# ECU_Sheet.net
KiCad netlist of a schematic drawn in Altium Designer
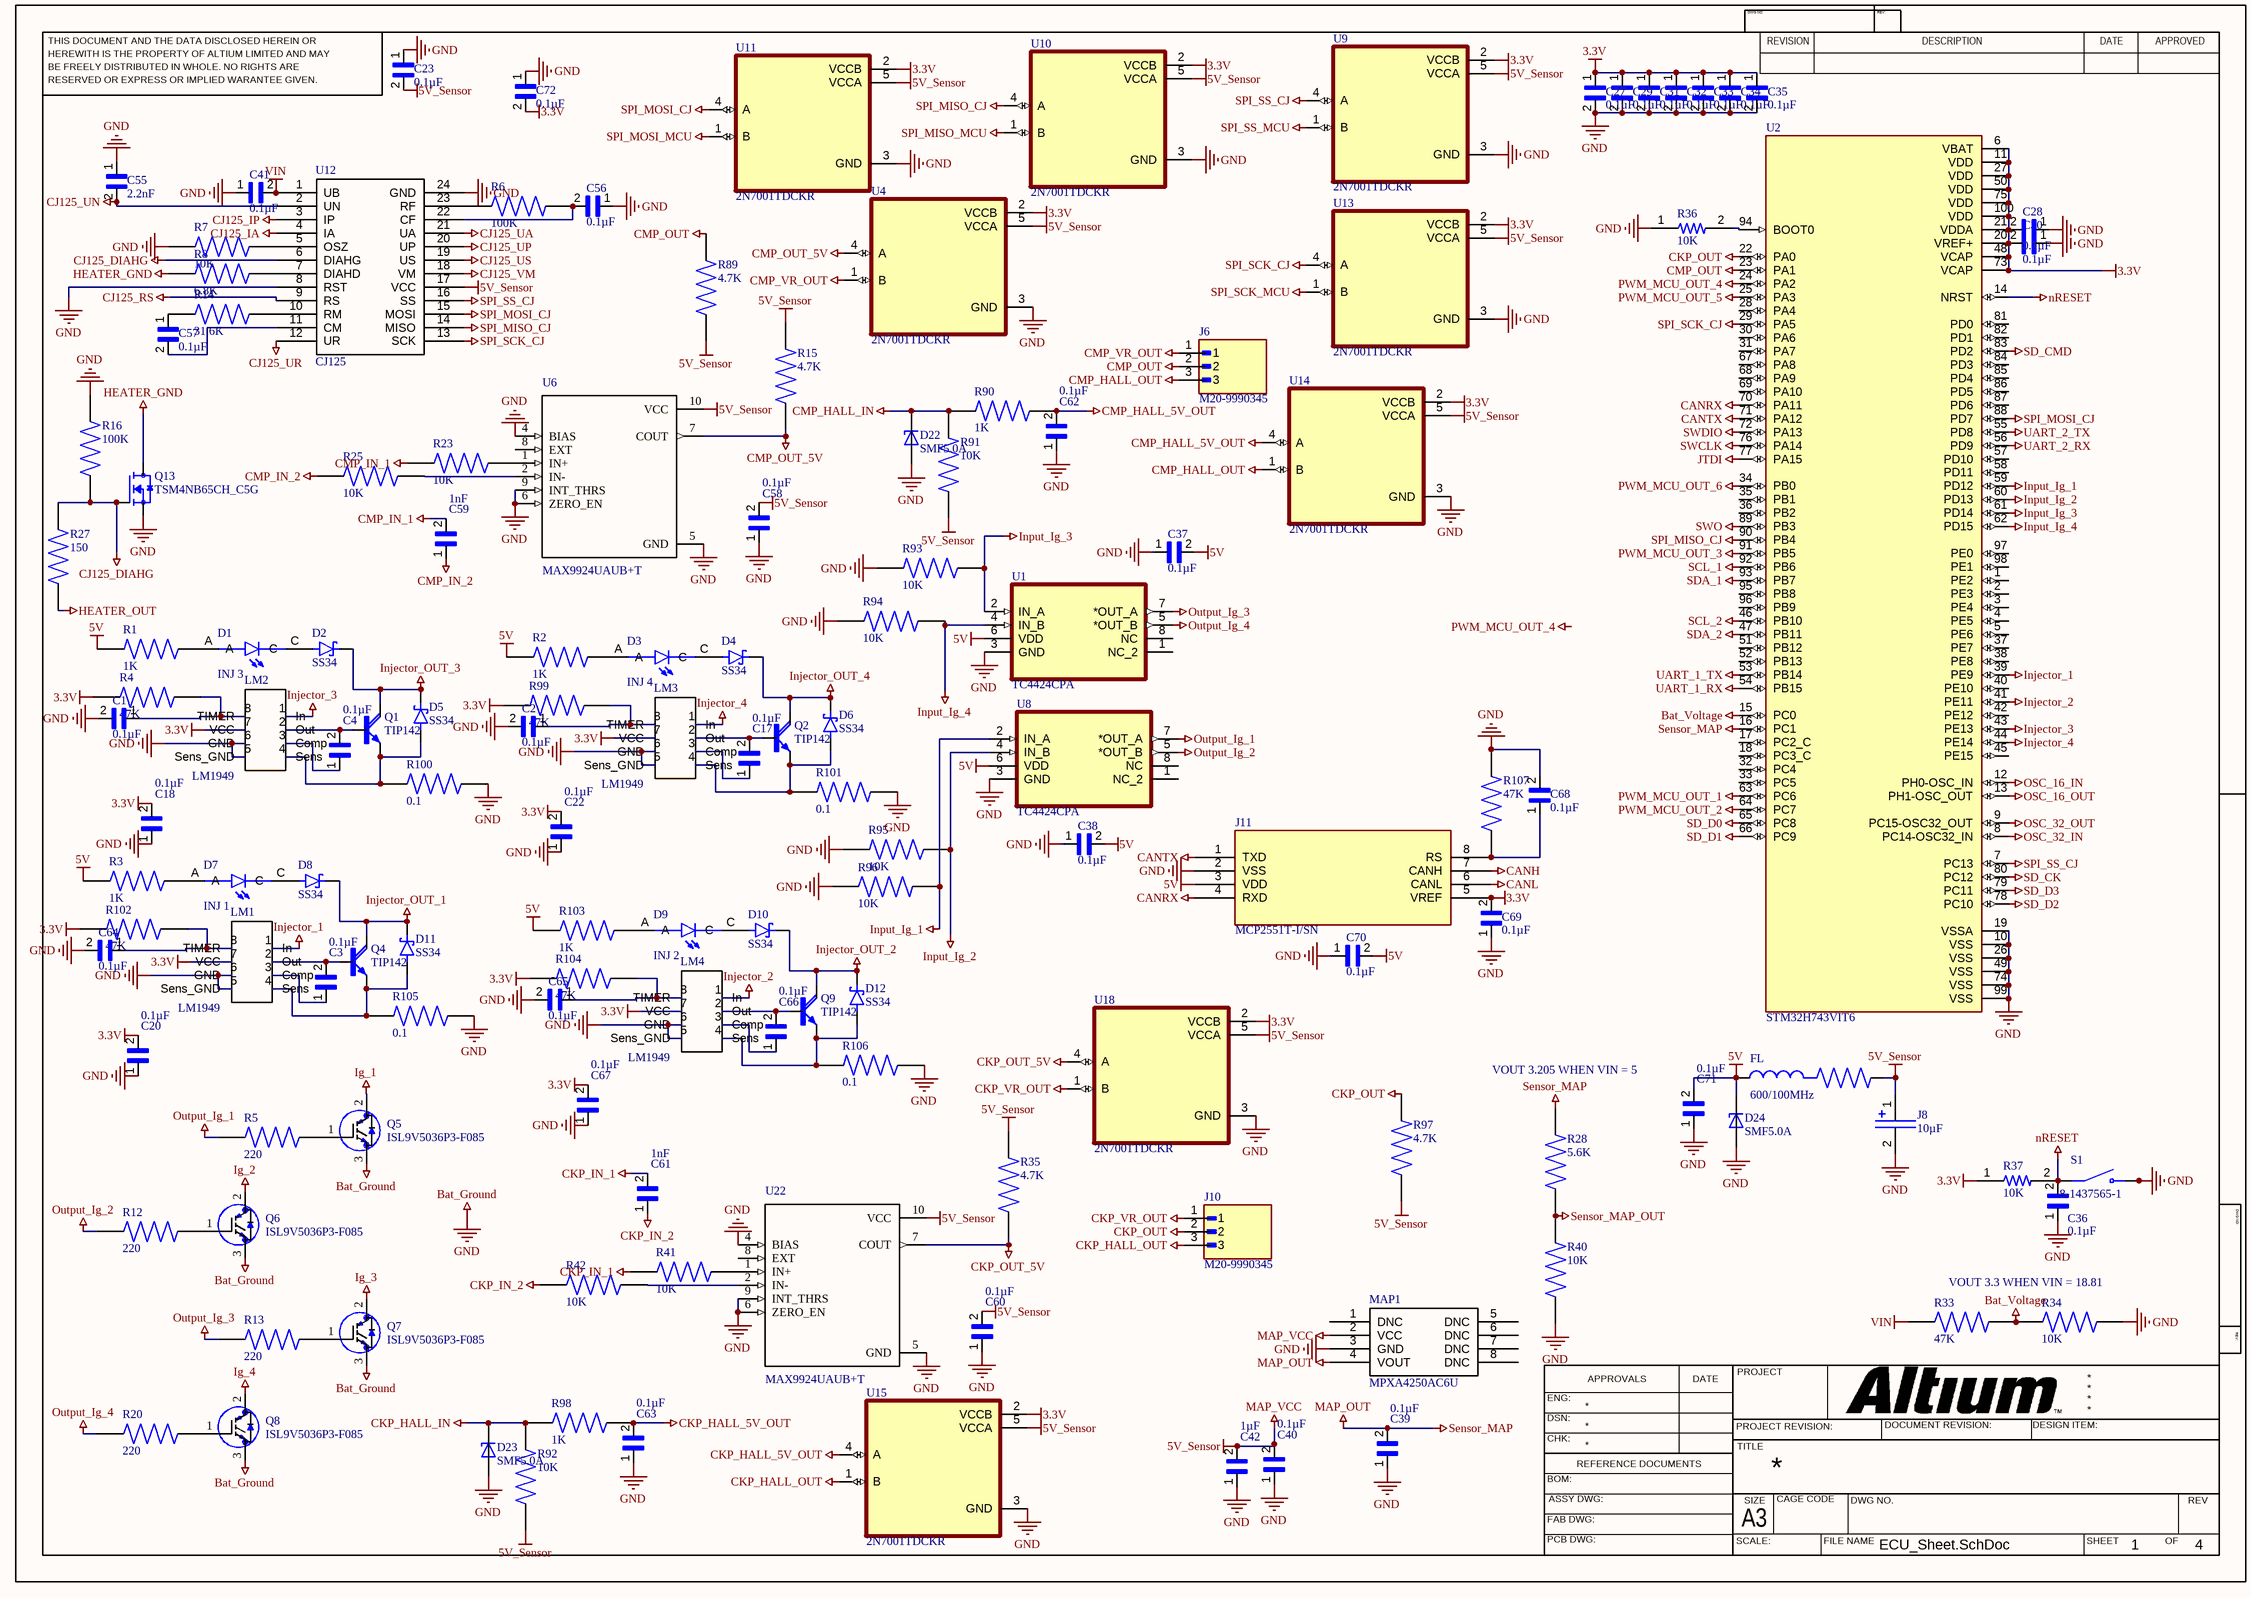
[diagram p0: ECU_Sheet.SchDoc]

(export (version "E")
  (design (tool "Eeschema 10.0.6"))
  (components
    (comp (ref "C1")
      (value "0.1µF")
      (footprint "CAPC1608X90N")
      (description "Multilayer Ceramic Capacitors MLCC - SMD/SMT")
      (fields (field (name "MP") "06035C104MAZ2A"))
      (libsource (lib "") (part "06035C104MAZ2A_1"))
    )
    (comp (ref "C2")
      (value "0.1µF")
      (footprint "CAPC1608X90N")
      (description "Multilayer Ceramic Capacitors MLCC - SMD/SMT")
      (fields (field (name "MP") "06035C104MAZ2A"))
      (libsource (lib "") (part "06035C104MAZ2A_1"))
    )
    (comp (ref "C3")
      (value "0.1µF")
      (footprint "CAPC1608X90N")
      (description "Multilayer Ceramic Capacitors MLCC - SMD/SMT")
      (fields (field (name "MP") "06035C104MAZ2A"))
      (libsource (lib "06035C104MAZ2A") (part "06035C104MAZ2A"))
    )
    (comp (ref "C4")
      (value "0.1µF")
      (footprint "CAPC1608X90N")
      (description "Multilayer Ceramic Capacitors MLCC - SMD/SMT")
      (fields (field (name "MP") "06035C104MAZ2A"))
      (libsource (lib "06035C104MAZ2A") (part "06035C104MAZ2A"))
    )
    (comp (ref "C17")
      (value "0.1µF")
      (footprint "CAPC1608X90N")
      (description "Multilayer Ceramic Capacitors MLCC - SMD/SMT")
      (fields (field (name "MP") "06035C104MAZ2A"))
      (libsource (lib "06035C104MAZ2A") (part "06035C104MAZ2A"))
    )
    (comp (ref "C18")
      (value "0.1µF")
      (footprint "CAPC1608X90N")
      (description "Multilayer Ceramic Capacitors MLCC - SMD/SMT")
      (fields (field (name "MP") "06035C104MAZ2A"))
      (libsource (lib "06035C104MAZ2A") (part "06035C104MAZ2A"))
    )
    (comp (ref "C20")
      (value "0.1µF")
      (footprint "CAPC1608X90N")
      (description "Multilayer Ceramic Capacitors MLCC - SMD/SMT")
      (fields (field (name "MP") "06035C104MAZ2A"))
      (libsource (lib "06035C104MAZ2A") (part "06035C104MAZ2A"))
    )
    (comp (ref "C22")
      (value "0.1µF")
      (footprint "CAPC1608X90N")
      (description "Multilayer Ceramic Capacitors MLCC - SMD/SMT")
      (fields (field (name "MP") "06035C104MAZ2A"))
      (libsource (lib "06035C104MAZ2A") (part "06035C104MAZ2A"))
    )
    (comp (ref "C23")
      (value "0.1µF")
      (footprint "CAPC1608X90N")
      (description "Multilayer Ceramic Capacitors MLCC - SMD/SMT")
      (fields (field (name "MP") "06035C104MAZ2A"))
      (libsource (lib "") (part "06035C104MAZ2A_2"))
    )
    (comp (ref "C27")
      (value "0.1µF")
      (footprint "CAPC1608X90N")
      (description "Multilayer Ceramic Capacitors MLCC - SMD/SMT")
      (fields (field (name "MP") "06035C104MAZ2A"))
      (libsource (lib "") (part "06035C104MAZ2A_2"))
    )
    (comp (ref "C28")
      (value "0.1µF")
      (footprint "CAPC1608X90N")
      (description "Multilayer Ceramic Capacitors MLCC - SMD/SMT")
      (fields (field (name "MP") "06035C104MAZ2A"))
      (libsource (lib "") (part "06035C104MAZ2A_1"))
    )
    (comp (ref "C29")
      (value "0.1µF")
      (footprint "CAPC1608X90N")
      (description "Multilayer Ceramic Capacitors MLCC - SMD/SMT")
      (fields (field (name "MP") "06035C104MAZ2A"))
      (libsource (lib "") (part "06035C104MAZ2A_2"))
    )
    (comp (ref "C30")
      (value "0.1µF")
      (footprint "CAPC1608X90N")
      (description "Multilayer Ceramic Capacitors MLCC - SMD/SMT")
      (fields (field (name "MP") "06035C104MAZ2A"))
      (libsource (lib "") (part "06035C104MAZ2A_1"))
    )
    (comp (ref "C31")
      (value "0.1µF")
      (footprint "CAPC1608X90N")
      (description "Multilayer Ceramic Capacitors MLCC - SMD/SMT")
      (fields (field (name "MP") "06035C104MAZ2A"))
      (libsource (lib "") (part "06035C104MAZ2A_2"))
    )
    (comp (ref "C32")
      (value "0.1µF")
      (footprint "CAPC1608X90N")
      (description "Multilayer Ceramic Capacitors MLCC - SMD/SMT")
      (fields (field (name "MP") "06035C104MAZ2A"))
      (libsource (lib "") (part "06035C104MAZ2A_2"))
    )
    (comp (ref "C33")
      (value "0.1µF")
      (footprint "CAPC1608X90N")
      (description "Multilayer Ceramic Capacitors MLCC - SMD/SMT")
      (fields (field (name "MP") "06035C104MAZ2A"))
      (libsource (lib "") (part "06035C104MAZ2A_2"))
    )
    (comp (ref "C34")
      (value "0.1µF")
      (footprint "CAPC1608X90N")
      (description "Multilayer Ceramic Capacitors MLCC - SMD/SMT")
      (fields (field (name "MP") "06035C104MAZ2A"))
      (libsource (lib "") (part "06035C104MAZ2A_2"))
    )
    (comp (ref "C35")
      (value "0.1µF")
      (footprint "CAPC1608X90N")
      (description "Multilayer Ceramic Capacitors MLCC - SMD/SMT")
      (fields (field (name "MP") "06035C104MAZ2A"))
      (libsource (lib "") (part "06035C104MAZ2A_2"))
    )
    (comp (ref "C36")
      (value "0.1µF")
      (footprint "CAPC1608X90N")
      (description "Multilayer Ceramic Capacitors MLCC - SMD/SMT")
      (fields (field (name "MP") "06035C104MAZ2A"))
      (libsource (lib "06035C104MAZ2A") (part "06035C104MAZ2A"))
    )
    (comp (ref "C37")
      (value "0.1µF")
      (footprint "CAPC1608X90N")
      (description "Multilayer Ceramic Capacitors MLCC - SMD/SMT")
      (fields (field (name "MP") "06035C104MAZ2A"))
      (libsource (lib "") (part "06035C104MAZ2A_3"))
    )
    (comp (ref "C38")
      (value "0.1µF")
      (footprint "CAPC1608X90N")
      (description "Multilayer Ceramic Capacitors MLCC - SMD/SMT")
      (fields (field (name "MP") "06035C104MAZ2A"))
      (libsource (lib "") (part "06035C104MAZ2A_3"))
    )
    (comp (ref "C39")
      (value "0.1µF")
      (footprint "CAPC1608X90N")
      (description "Multilayer Ceramic Capacitors MLCC - SMD/SMT")
      (fields (field (name "MP") "06035C104MAZ2A"))
      (libsource (lib "06035C104MAZ2A") (part "06035C104MAZ2A"))
    )
    (comp (ref "C40")
      (value "0.1µF")
      (footprint "CAPC1608X90N")
      (description "Multilayer Ceramic Capacitors MLCC - SMD/SMT")
      (fields (field (name "MP") "06035C104MAZ2A"))
      (libsource (lib "06035C104MAZ2A") (part "06035C104MAZ2A"))
    )
    (comp (ref "C41")
      (value "0.1µF")
      (footprint "CAPC1608X90N")
      (description "Multilayer Ceramic Capacitors MLCC - SMD/SMT")
      (fields (field (name "MP") "06035C104MAZ2A"))
      (libsource (lib "") (part "06035C104MAZ2A_3"))
    )
    (comp (ref "C42")
      (value "1µF")
      (footprint "CAPC1608X90N")
      (description "Multilayer Ceramic Capacitors MLCC - SMD/SMT")
      (fields (field (name "MP") "06035C104MAZ2A"))
      (libsource (lib "06035C104MAZ2A") (part "06035C104MAZ2A"))
    )
    (comp (ref "C55")
      (value "2.2nF")
      (footprint "CAPC1608X90N")
      (description "Multilayer Ceramic Capacitors MLCC - SMD/SMT")
      (fields (field (name "MP") "06035C104MAZ2A"))
      (libsource (lib "") (part "06035C104MAZ2A_2"))
    )
    (comp (ref "C56")
      (value "0.1µF")
      (footprint "CAPC1608X90N")
      (description "Multilayer Ceramic Capacitors MLCC - SMD/SMT")
      (fields (field (name "MP") "06035C104MAZ2A"))
      (libsource (lib "") (part "06035C104MAZ2A_1"))
    )
    (comp (ref "C57")
      (value "0.1µF")
      (footprint "CAPC1608X90N")
      (description "Multilayer Ceramic Capacitors MLCC - SMD/SMT")
      (fields (field (name "MP") "06035C104MAZ2A"))
      (libsource (lib "") (part "06035C104MAZ2A_2"))
    )
    (comp (ref "C58")
      (value "0.1µF")
      (footprint "CAPC1608X90N")
      (description "Multilayer Ceramic Capacitors MLCC - SMD/SMT")
      (fields (field (name "MP") "06035C104MAZ2A"))
      (libsource (lib "06035C104MAZ2A") (part "06035C104MAZ2A"))
    )
    (comp (ref "C59")
      (value "1nF")
      (footprint "CAPC1608X90N")
      (description "Multilayer Ceramic Capacitors MLCC - SMD/SMT")
      (fields (field (name "MP") "06035C104MAZ2A"))
      (libsource (lib "06035C104MAZ2A") (part "06035C104MAZ2A"))
    )
    (comp (ref "C60")
      (value "0.1µF")
      (footprint "CAPC1608X90N")
      (description "Multilayer Ceramic Capacitors MLCC - SMD/SMT")
      (fields (field (name "MP") "06035C104MAZ2A"))
      (libsource (lib "06035C104MAZ2A") (part "06035C104MAZ2A"))
    )
    (comp (ref "C61")
      (value "1nF")
      (footprint "CAPC1608X90N")
      (description "Multilayer Ceramic Capacitors MLCC - SMD/SMT")
      (fields (field (name "MP") "06035C104MAZ2A"))
      (libsource (lib "06035C104MAZ2A") (part "06035C104MAZ2A"))
    )
    (comp (ref "C62")
      (value "0.1µF")
      (footprint "CAPC1608X90N")
      (description "Multilayer Ceramic Capacitors MLCC - SMD/SMT")
      (fields (field (name "MP") "06035C104MAZ2A"))
      (libsource (lib "06035C104MAZ2A") (part "06035C104MAZ2A"))
    )
    (comp (ref "C63")
      (value "0.1µF")
      (footprint "CAPC1608X90N")
      (description "Multilayer Ceramic Capacitors MLCC - SMD/SMT")
      (fields (field (name "MP") "06035C104MAZ2A"))
      (libsource (lib "06035C104MAZ2A") (part "06035C104MAZ2A"))
    )
    (comp (ref "C64")
      (value "0.1µF")
      (footprint "CAPC1608X90N")
      (description "Multilayer Ceramic Capacitors MLCC - SMD/SMT")
      (fields (field (name "MP") "06035C104MAZ2A"))
      (libsource (lib "") (part "06035C104MAZ2A_1"))
    )
    (comp (ref "C65")
      (value "0.1µF")
      (footprint "CAPC1608X90N")
      (description "Multilayer Ceramic Capacitors MLCC - SMD/SMT")
      (fields (field (name "MP") "06035C104MAZ2A"))
      (libsource (lib "") (part "06035C104MAZ2A_1"))
    )
    (comp (ref "C66")
      (value "0.1µF")
      (footprint "CAPC1608X90N")
      (description "Multilayer Ceramic Capacitors MLCC - SMD/SMT")
      (fields (field (name "MP") "06035C104MAZ2A"))
      (libsource (lib "06035C104MAZ2A") (part "06035C104MAZ2A"))
    )
    (comp (ref "C67")
      (value "0.1µF")
      (footprint "CAPC1608X90N")
      (description "Multilayer Ceramic Capacitors MLCC - SMD/SMT")
      (fields (field (name "MP") "06035C104MAZ2A"))
      (libsource (lib "06035C104MAZ2A") (part "06035C104MAZ2A"))
    )
    (comp (ref "C68")
      (value "0.1µF")
      (footprint "CAPC1608X90N")
      (description "Multilayer Ceramic Capacitors MLCC - SMD/SMT")
      (fields (field (name "MP") "06035C104MAZ2A"))
      (libsource (lib "06035C104MAZ2A") (part "06035C104MAZ2A"))
    )
    (comp (ref "C69")
      (value "0.1µF")
      (footprint "CAPC1608X90N")
      (description "Multilayer Ceramic Capacitors MLCC - SMD/SMT")
      (fields (field (name "MP") "06035C104MAZ2A"))
      (libsource (lib "06035C104MAZ2A") (part "06035C104MAZ2A"))
    )
    (comp (ref "C70")
      (value "0.1µF")
      (footprint "CAPC1608X90N")
      (description "Multilayer Ceramic Capacitors MLCC - SMD/SMT")
      (fields (field (name "MP") "06035C104MAZ2A"))
      (libsource (lib "") (part "06035C104MAZ2A_3"))
    )
    (comp (ref "C71")
      (value "0.1µF")
      (footprint "CAPC1608X90N")
      (description "Multilayer Ceramic Capacitors MLCC - SMD/SMT")
      (fields (field (name "MP") "06035C104MAZ2A"))
      (libsource (lib "06035C104MAZ2A") (part "06035C104MAZ2A"))
    )
    (comp (ref "C72")
      (value "0.1µF")
      (footprint "CAPC1608X90N")
      (description "Multilayer Ceramic Capacitors MLCC - SMD/SMT")
      (fields (field (name "MP") "06035C104MAZ2A"))
      (libsource (lib "") (part "06035C104MAZ2A_2"))
    )
    (comp (ref "D1")
      (value "INJ 3")
      (footprint "LEDC2012X70N")
      (description "LED Uni-Color Green 4-Pin Chip 0805 T/R")
      (fields (field (name "MP") "597-3305-607F"))
      (libsource (lib "597-3305-607F") (part "597-3305-607F"))
    )
    (comp (ref "D2")
      (value "SS34")
      (footprint "DIO_SS34")
      (description "3A, 40V, Schottky Rectifier")
      (fields (field (name "MF") "Taiwan Semiconductor"))
      (libsource (lib "SS34") (part "SS34"))
    )
    (comp (ref "D3")
      (value "INJ 4")
      (footprint "LEDC2012X70N")
      (description "LED Uni-Color Green 4-Pin Chip 0805 T/R")
      (fields (field (name "MP") "597-3305-607F"))
      (libsource (lib "597-3305-607F") (part "597-3305-607F"))
    )
    (comp (ref "D4")
      (value "SS34")
      (footprint "DIO_SS34")
      (description "3A, 40V, Schottky Rectifier")
      (fields (field (name "MF") "Taiwan Semiconductor"))
      (libsource (lib "SS34") (part "SS34"))
    )
    (comp (ref "D5")
      (value "SS34")
      (footprint "DIO_SS34")
      (description "3A, 40V, Schottky Rectifier")
      (fields (field (name "MF") "Taiwan Semiconductor"))
      (libsource (lib "SS34") (part "SS34"))
    )
    (comp (ref "D6")
      (value "SS34")
      (footprint "DIO_SS34")
      (description "3A, 40V, Schottky Rectifier")
      (fields (field (name "MF") "Taiwan Semiconductor"))
      (libsource (lib "SS34") (part "SS34"))
    )
    (comp (ref "D7")
      (value "INJ 1")
      (footprint "LEDC2012X70N")
      (description "LED Uni-Color Green 4-Pin Chip 0805 T/R")
      (fields (field (name "MP") "597-3305-607F"))
      (libsource (lib "597-3305-607F") (part "597-3305-607F"))
    )
    (comp (ref "D8")
      (value "SS34")
      (footprint "DIO_SS34")
      (description "3A, 40V, Schottky Rectifier")
      (fields (field (name "MF") "Taiwan Semiconductor"))
      (libsource (lib "SS34") (part "SS34"))
    )
    (comp (ref "D9")
      (value "INJ 2")
      (footprint "LEDC2012X70N")
      (description "LED Uni-Color Green 4-Pin Chip 0805 T/R")
      (fields (field (name "MP") "597-3305-607F"))
      (libsource (lib "597-3305-607F") (part "597-3305-607F"))
    )
    (comp (ref "D10")
      (value "SS34")
      (footprint "DIO_SS34")
      (description "3A, 40V, Schottky Rectifier")
      (fields (field (name "MF") "Taiwan Semiconductor"))
      (libsource (lib "SS34") (part "SS34"))
    )
    (comp (ref "D11")
      (value "SS34")
      (footprint "DIO_SS34")
      (description "3A, 40V, Schottky Rectifier")
      (fields (field (name "MF") "Taiwan Semiconductor"))
      (libsource (lib "SS34") (part "SS34"))
    )
    (comp (ref "D12")
      (value "SS34")
      (footprint "DIO_SS34")
      (description "3A, 40V, Schottky Rectifier")
      (fields (field (name "MF") "Taiwan Semiconductor"))
      (libsource (lib "SS34") (part "SS34"))
    )
    (comp (ref "D22")
      (value "SMF5.0A")
      (footprint "SODFL3718X102N")
      (description "200W, 6.7V, 5%, Unidirectional, TVS")
      (fields (field (name "MF") "Taiwan Semiconductor"))
      (libsource (lib "SMF5.0A") (part "SMF5.0A"))
    )
    (comp (ref "D23")
      (value "SMF5.0A")
      (footprint "SODFL3718X102N")
      (description "200W, 6.7V, 5%, Unidirectional, TVS")
      (fields (field (name "MF") "Taiwan Semiconductor"))
      (libsource (lib "SMF5.0A") (part "SMF5.0A"))
    )
    (comp (ref "D24")
      (value "SMF5.0A")
      (footprint "SODFL3718X102N")
      (description "200W, 6.7V, 5%, Unidirectional, TVS")
      (fields (field (name "MF") "Taiwan Semiconductor"))
      (libsource (lib "SMF5.0A") (part "SMF5.0A"))
    )
    (comp (ref "FL")
      (value "600/100MHz")
      (footprint "BEADC1608X95N")
      (description "600 Ohms @ 100MHz 1 Ferrite Bead 0603 _1608 Metric_ 700mA")
      (fields (field (name "MF") "Murata") (field (name "MP") "BLM18DN601SZ1D"))
      (libsource (lib "BLM18DN601SZ1D") (part "BLM18DN601SZ1D"))
    )
    (comp (ref "J6")
      (value "M20-9990345")
      (footprint "HARWIN_M20-9990345")
      (fields (field (name "MF") "Harwin"))
      (libsource (lib "M20-9990345") (part "M20-9990345"))
    )
    (comp (ref "J8")
      (value "10µF")
      (footprint "T491A106K010AT")
      (fields (field (name "MF") "KEMET") (field (name "MP") "T491A106K010AT"))
      (libsource (lib "T491A106K010AT") (part "T491A106K010AT"))
    )
    (comp (ref "J10")
      (value "M20-9990345")
      (footprint "HARWIN_M20-9990345")
      (fields (field (name "MF") "Harwin"))
      (libsource (lib "M20-9990345") (part "M20-9990345"))
    )
    (comp (ref "J11")
      (value "MCP2551T-I/SN")
      (footprint "SOIC8-N_MC")
      (fields (field (name "MF") "Microchip"))
      (libsource (lib "MCP2551T-I_SN") (part "MCP2551T-I/SN"))
    )
    (comp (ref "LM1")
      (value "LM1949")
      (footprint "DIP794W45P254L959H508Q8")
      (libsource (lib "LM1949") (part "Component_1"))
    )
    (comp (ref "LM2")
      (value "LM1949")
      (footprint "DIP794W45P254L959H508Q8")
      (libsource (lib "LM1949") (part "Component_1"))
    )
    (comp (ref "LM3")
      (value "LM1949")
      (footprint "DIP794W45P254L959H508Q8")
      (libsource (lib "LM1949") (part "Component_1"))
    )
    (comp (ref "LM4")
      (value "LM1949")
      (footprint "DIP794W45P254L959H508Q8")
      (libsource (lib "LM1949") (part "Component_1"))
    )
    (comp (ref "MAP1")
      (value "MPXA4250AC6U")
      (footprint "SOIC127P1041X990-8N:SOIC127P1041X990-8N")
      (libsource (lib "MPXA4250A") (part "MPXA4250AC6U"))
    )
    (comp (ref "Q1")
      (value "TIP142")
      (footprint "SOT93")
      (description "Bipolar (BJT) Transistor NPN - Darlington 100 V 10 A - 125 W Through Hole TO-247-3")
      (fields (field (name "MF") "ON Semiconductor"))
      (libsource (lib "TIP142") (part "TIP142"))
    )
    (comp (ref "Q2")
      (value "TIP142")
      (footprint "SOT93")
      (description "Bipolar (BJT) Transistor NPN - Darlington 100 V 10 A - 125 W Through Hole TO-247-3")
      (fields (field (name "MF") "ON Semiconductor"))
      (libsource (lib "TIP142") (part "TIP142"))
    )
    (comp (ref "Q4")
      (value "TIP142")
      (footprint "SOT93")
      (description "Bipolar (BJT) Transistor NPN - Darlington 100 V 10 A - 125 W Through Hole TO-247-3")
      (fields (field (name "MF") "ON Semiconductor"))
      (libsource (lib "TIP142") (part "TIP142"))
    )
    (comp (ref "Q5")
      (value "ISL9V5036P3-F085")
      (footprint "*TO254P470X1016X2019-3P")
      (libsource (lib "ISL9V5036P3-F085") (part "ISL9V5036P3-F085"))
    )
    (comp (ref "Q6")
      (value "ISL9V5036P3-F085")
      (footprint "*TO254P470X1016X2019-3P")
      (libsource (lib "ISL9V5036P3-F085") (part "ISL9V5036P3-F085"))
    )
    (comp (ref "Q7")
      (value "ISL9V5036P3-F085")
      (footprint "*TO254P470X1016X2019-3P")
      (libsource (lib "ISL9V5036P3-F085") (part "ISL9V5036P3-F085"))
    )
    (comp (ref "Q8")
      (value "ISL9V5036P3-F085")
      (footprint "*TO254P470X1016X2019-3P")
      (libsource (lib "ISL9V5036P3-F085") (part "ISL9V5036P3-F085"))
    )
    (comp (ref "Q9")
      (value "TIP142")
      (footprint "SOT93")
      (description "Bipolar (BJT) Transistor NPN - Darlington 100 V 10 A - 125 W Through Hole TO-247-3")
      (fields (field (name "MF") "ON Semiconductor"))
      (libsource (lib "TIP142") (part "TIP142"))
    )
    (comp (ref "Q13")
      (value "TSM4NB65CH_C5G")
      (footprint "TO228P680X240X837-3")
      (description "650V, 4A, Single N-Channel Power MOSFET")
      (fields (field (name "MF") "Taiwan Semiconductor") (field (name "MP") "TSM4NB65CH C5G"))
      (libsource (lib "TSM4NB65CH_C5G") (part "TSM4NB65CH_C5G"))
    )
    (comp (ref "R1")
      (value "1K")
      (footprint "RESC3116X65N")
      (fields (field (name "MF") "Yageo Corporation") (field (name "MP") "RC1206JR071KL"))
      (libsource (lib "RC1206JR-071KL") (part "RC1206JR-071KL"))
    )
    (comp (ref "R2")
      (value "1K")
      (footprint "RESC3116X65N")
      (fields (field (name "MF") "Yageo Corporation") (field (name "MP") "RC1206JR071KL"))
      (libsource (lib "RC1206JR-071KL") (part "RC1206JR-071KL"))
    )
    (comp (ref "R3")
      (value "1K")
      (footprint "RESC3116X65N")
      (fields (field (name "MF") "Yageo Corporation") (field (name "MP") "RC1206JR071KL"))
      (libsource (lib "RC1206JR-071KL") (part "RC1206JR-071KL"))
    )
    (comp (ref "R4")
      (value "47K")
      (footprint "RESC3116X65N")
      (fields (field (name "MP") "AA1206JR-07470RL"))
      (libsource (lib "AA1206JR-07470RL") (part "AA1206JR-07470RL"))
    )
    (comp (ref "R5")
      (value "220")
      (footprint "RES_ERJP08J221V")
      (fields (field (name "MP") "ERJP08J221V"))
      (libsource (lib "ERJP08J221V") (part "ERJP08J221V"))
    )
    (comp (ref "R6")
      (value "100K")
      (footprint "RESC3116X65N")
      (fields (field (name "MP") "AA1206JR-07470RL"))
      (libsource (lib "AA1206JR-07470RL") (part "AA1206JR-07470RL"))
    )
    (comp (ref "R7")
      (value "10K")
      (footprint "RESC3116X65N")
      (fields (field (name "MP") "AA1206JR-07470RL"))
      (libsource (lib "AA1206JR-07470RL") (part "AA1206JR-07470RL"))
    )
    (comp (ref "R8")
      (value "6.8K")
      (footprint "RESC3116X65N")
      (fields (field (name "MP") "AA1206JR-07470RL"))
      (libsource (lib "AA1206JR-07470RL") (part "AA1206JR-07470RL"))
    )
    (comp (ref "R12")
      (value "220")
      (footprint "RES_ERJP08J221V")
      (fields (field (name "MP") "ERJP08J221V"))
      (libsource (lib "ERJP08J221V") (part "ERJP08J221V"))
    )
    (comp (ref "R13")
      (value "220")
      (footprint "RES_ERJP08J221V")
      (fields (field (name "MP") "ERJP08J221V"))
      (libsource (lib "ERJP08J221V") (part "ERJP08J221V"))
    )
    (comp (ref "R14")
      (value "31.6K")
      (footprint "RESC3116X65N")
      (fields (field (name "MP") "AA1206JR-07470RL"))
      (libsource (lib "AA1206JR-07470RL") (part "AA1206JR-07470RL"))
    )
    (comp (ref "R15")
      (value "4.7K")
      (footprint "RESC3116X65N")
      (fields (field (name "MP") "AA1206JR-07470RL"))
      (libsource (lib "AA1206JR-07470RL") (part "AA1206JR-07470RL"))
    )
    (comp (ref "R16")
      (value "100K")
      (footprint "RESC3116X65N")
      (fields (field (name "MP") "AA1206JR-07470RL"))
      (libsource (lib "AA1206JR-07470RL") (part "AA1206JR-07470RL"))
    )
    (comp (ref "R20")
      (value "220")
      (footprint "RES_ERJP08J221V")
      (fields (field (name "MP") "ERJP08J221V"))
      (libsource (lib "ERJP08J221V") (part "ERJP08J221V"))
    )
    (comp (ref "R23")
      (value "10K")
      (footprint "RESC3116X65N")
      (fields (field (name "MP") "AA1206JR-07470RL"))
      (libsource (lib "AA1206JR-07470RL") (part "AA1206JR-07470RL"))
    )
    (comp (ref "R25")
      (value "10K")
      (footprint "RESC3116X65N")
      (fields (field (name "MP") "AA1206JR-07470RL"))
      (libsource (lib "AA1206JR-07470RL") (part "AA1206JR-07470RL"))
    )
    (comp (ref "R27")
      (value "150")
      (footprint "RESC3116X65N")
      (fields (field (name "MP") "AA1206JR-07470RL"))
      (libsource (lib "AA1206JR-07470RL") (part "AA1206JR-07470RL"))
    )
    (comp (ref "R28")
      (value "5.6K")
      (footprint "RESC3116X65N")
      (fields (field (name "MP") "AA1206JR-07470RL"))
      (libsource (lib "AA1206JR-07470RL") (part "AA1206JR-07470RL"))
    )
    (comp (ref "R33")
      (value "47K")
      (footprint "RESC3116X65N")
      (fields (field (name "MP") "AA1206JR-07470RL"))
      (libsource (lib "AA1206JR-07470RL") (part "AA1206JR-07470RL"))
    )
    (comp (ref "R34")
      (value "10K")
      (footprint "RESC3116X65N")
      (fields (field (name "MP") "AA1206JR-07470RL"))
      (libsource (lib "AA1206JR-07470RL") (part "AA1206JR-07470RL"))
    )
    (comp (ref "R35")
      (value "4.7K")
      (footprint "RESC3116X65N")
      (fields (field (name "MP") "AA1206JR-07470RL"))
      (libsource (lib "AA1206JR-07470RL") (part "AA1206JR-07470RL"))
    )
    (comp (ref "R36")
      (value "10K")
      (footprint "RESC1608X50N")
      (description "Thin Film Resistors - SMD 10K OHM .1% 25PPM")
      (fields (field (name "MP") "RP73PF1J10KBTDF") (field (name "TOLERANCE") ".1%"))
      (libsource (lib "RP73PF1J10KBTDF") (part "RP73PF1J10KBTDF"))
    )
    (comp (ref "R37")
      (value "10K")
      (footprint "RESC1608X50N")
      (description "Thin Film Resistors - SMD 10K OHM .1% 25PPM")
      (fields (field (name "MP") "RP73PF1J10KBTDF") (field (name "TOLERANCE") ".1%"))
      (libsource (lib "RP73PF1J10KBTDF") (part "RP73PF1J10KBTDF"))
    )
    (comp (ref "R40")
      (value "10K")
      (footprint "RESC3116X65N")
      (fields (field (name "MP") "AA1206JR-07470RL"))
      (libsource (lib "AA1206JR-07470RL") (part "AA1206JR-07470RL"))
    )
    (comp (ref "R41")
      (value "10K")
      (footprint "RESC3116X65N")
      (fields (field (name "MP") "AA1206JR-07470RL"))
      (libsource (lib "AA1206JR-07470RL") (part "AA1206JR-07470RL"))
    )
    (comp (ref "R42")
      (value "10K")
      (footprint "RESC3116X65N")
      (fields (field (name "MP") "AA1206JR-07470RL"))
      (libsource (lib "AA1206JR-07470RL") (part "AA1206JR-07470RL"))
    )
    (comp (ref "R89")
      (value "4.7K")
      (footprint "RESC3116X65N")
      (fields (field (name "MP") "AA1206JR-07470RL"))
      (libsource (lib "AA1206JR-07470RL") (part "AA1206JR-07470RL"))
    )
    (comp (ref "R90")
      (value "1K")
      (footprint "RESC3116X65N")
      (fields (field (name "MP") "AA1206JR-07470RL"))
      (libsource (lib "AA1206JR-07470RL") (part "AA1206JR-07470RL"))
    )
    (comp (ref "R91")
      (value "10K")
      (footprint "RESC3116X65N")
      (fields (field (name "MP") "AA1206JR-07470RL"))
      (libsource (lib "AA1206JR-07470RL") (part "AA1206JR-07470RL"))
    )
    (comp (ref "R92")
      (value "10K")
      (footprint "RESC3116X65N")
      (fields (field (name "MP") "AA1206JR-07470RL"))
      (libsource (lib "AA1206JR-07470RL") (part "AA1206JR-07470RL"))
    )
    (comp (ref "R93")
      (value "10K")
      (footprint "RESC3116X65N")
      (fields (field (name "MP") "AA1206JR-07470RL"))
      (libsource (lib "AA1206JR-07470RL") (part "AA1206JR-07470RL"))
    )
    (comp (ref "R94")
      (value "10K")
      (footprint "RESC3116X65N")
      (fields (field (name "MP") "AA1206JR-07470RL"))
      (libsource (lib "AA1206JR-07470RL") (part "AA1206JR-07470RL"))
    )
    (comp (ref "R95")
      (value "10K")
      (footprint "RESC3116X65N")
      (fields (field (name "MP") "AA1206JR-07470RL"))
      (libsource (lib "AA1206JR-07470RL") (part "AA1206JR-07470RL"))
    )
    (comp (ref "R96")
      (value "10K")
      (footprint "RESC3116X65N")
      (fields (field (name "MP") "AA1206JR-07470RL"))
      (libsource (lib "AA1206JR-07470RL") (part "AA1206JR-07470RL"))
    )
    (comp (ref "R97")
      (value "4.7K")
      (footprint "RESC3116X65N")
      (fields (field (name "MP") "AA1206JR-07470RL"))
      (libsource (lib "AA1206JR-07470RL") (part "AA1206JR-07470RL"))
    )
    (comp (ref "R98")
      (value "1K")
      (footprint "RESC3116X65N")
      (fields (field (name "MP") "AA1206JR-07470RL"))
      (libsource (lib "AA1206JR-07470RL") (part "AA1206JR-07470RL"))
    )
    (comp (ref "R99")
      (value "47K")
      (footprint "RESC3116X65N")
      (fields (field (name "MP") "AA1206JR-07470RL"))
      (libsource (lib "AA1206JR-07470RL") (part "AA1206JR-07470RL"))
    )
    (comp (ref "R100")
      (value "0.1")
      (footprint "RES_ERJ6RSFR10V")
      (fields (field (name "MP") "ERJ6RSFR10V"))
      (libsource (lib "ERJ6RSFR10V") (part "ERJ6RSFR10V"))
    )
    (comp (ref "R101")
      (value "0.1")
      (footprint "RES_ERJ6RSFR10V")
      (fields (field (name "MP") "ERJ6RSFR10V"))
      (libsource (lib "ERJ6RSFR10V") (part "ERJ6RSFR10V"))
    )
    (comp (ref "R102")
      (value "47K")
      (footprint "RESC3116X65N")
      (fields (field (name "MP") "AA1206JR-07470RL"))
      (libsource (lib "AA1206JR-07470RL") (part "AA1206JR-07470RL"))
    )
    (comp (ref "R103")
      (value "1K")
      (footprint "RESC3116X65N")
      (fields (field (name "MF") "Yageo Corporation") (field (name "MP") "RC1206JR071KL"))
      (libsource (lib "RC1206JR-071KL") (part "RC1206JR-071KL"))
    )
    (comp (ref "R104")
      (value "47K")
      (footprint "RESC3116X65N")
      (fields (field (name "MP") "AA1206JR-07470RL"))
      (libsource (lib "AA1206JR-07470RL") (part "AA1206JR-07470RL"))
    )
    (comp (ref "R105")
      (value "0.1")
      (footprint "RES_ERJ6RSFR10V")
      (fields (field (name "MP") "ERJ6RSFR10V"))
      (libsource (lib "ERJ6RSFR10V") (part "ERJ6RSFR10V"))
    )
    (comp (ref "R106")
      (value "0.1")
      (footprint "RES_ERJ6RSFR10V")
      (fields (field (name "MP") "ERJ6RSFR10V"))
      (libsource (lib "ERJ6RSFR10V") (part "ERJ6RSFR10V"))
    )
    (comp (ref "R107")
      (value "47K")
      (footprint "RESC3116X65N")
      (fields (field (name "MP") "AA1206JR-07470RL"))
      (libsource (lib "AA1206JR-07470RL") (part "AA1206JR-07470RL"))
    )
    (comp (ref "S1")
      (value "8-1437565-1")
      (footprint "SW_8-1437565-1")
      (libsource (lib "8-1437565-1") (part "8-1437565-1"))
    )
    (comp (ref "U1")
      (value "TC4424CPA")
      (footprint "DIP254P762X432-8")
      (fields (field (name "MF") "Microchip"))
      (libsource (lib "TC4424CPA") (part "TC4424CPA"))
    )
    (comp (ref "U2")
      (value "STM32H743VIT6")
      (footprint "QFP50P1600X1600X160-100N")
      (fields (field (name "MF") "STMicroelectronics"))
      (libsource (lib "STM32H743VIT6") (part "STM32H743VIT6"))
    )
    (comp (ref "U4")
      (value "2N7001TDCKR")
      (footprint "SOT65P210X110-5N")
      (description "1-bit dual-supply buffered voltage signal converter")
      (fields (field (name "MF") "Texas Instruments"))
      (libsource (lib "2N7001TDCKR") (part "2N7001TDCKR"))
    )
    (comp (ref "U6")
      (value "MAX9924UAUB+T")
      (footprint "*SOP50P490X110-10N")
      (libsource (lib "MAX9924UAUB_T") (part "MAX9924UAUB+T"))
    )
    (comp (ref "U8")
      (value "TC4424CPA")
      (footprint "DIP254P762X432-8")
      (fields (field (name "MF") "Microchip"))
      (libsource (lib "TC4424CPA") (part "TC4424CPA"))
    )
    (comp (ref "U9")
      (value "2N7001TDCKR")
      (footprint "SOT65P210X110-5N")
      (description "1-bit dual-supply buffered voltage signal converter")
      (fields (field (name "MF") "Texas Instruments"))
      (libsource (lib "2N7001TDCKR") (part "2N7001TDCKR"))
    )
    (comp (ref "U10")
      (value "2N7001TDCKR")
      (footprint "SOT65P210X110-5N")
      (description "1-bit dual-supply buffered voltage signal converter")
      (fields (field (name "MF") "Texas Instruments"))
      (libsource (lib "2N7001TDCKR") (part "2N7001TDCKR"))
    )
    (comp (ref "U11")
      (value "2N7001TDCKR")
      (footprint "SOT65P210X110-5N")
      (description "1-bit dual-supply buffered voltage signal converter")
      (fields (field (name "MF") "Texas Instruments"))
      (libsource (lib "2N7001TDCKR") (part "2N7001TDCKR"))
    )
    (comp (ref "U12") (value "CJ125") (footprint "CJ125") (libsource (lib "CJ125 SOIC24") (part "CJ125")))
    (comp (ref "U13")
      (value "2N7001TDCKR")
      (footprint "SOT65P210X110-5N")
      (description "1-bit dual-supply buffered voltage signal converter")
      (fields (field (name "MF") "Texas Instruments"))
      (libsource (lib "2N7001TDCKR") (part "2N7001TDCKR"))
    )
    (comp (ref "U14")
      (value "2N7001TDCKR")
      (footprint "SOT65P210X110-5N")
      (description "1-bit dual-supply buffered voltage signal converter")
      (fields (field (name "MF") "Texas Instruments"))
      (libsource (lib "2N7001TDCKR") (part "2N7001TDCKR"))
    )
    (comp (ref "U15")
      (value "2N7001TDCKR")
      (footprint "SOT65P210X110-5N")
      (description "1-bit dual-supply buffered voltage signal converter")
      (fields (field (name "MF") "Texas Instruments"))
      (libsource (lib "2N7001TDCKR") (part "2N7001TDCKR"))
    )
    (comp (ref "U18")
      (value "2N7001TDCKR")
      (footprint "SOT65P210X110-5N")
      (description "1-bit dual-supply buffered voltage signal converter")
      (fields (field (name "MF") "Texas Instruments"))
      (libsource (lib "2N7001TDCKR") (part "2N7001TDCKR"))
    )
    (comp (ref "U22")
      (value "MAX9924UAUB+T")
      (footprint "*SOP50P490X110-10N")
      (libsource (lib "MAX9924UAUB_T") (part "MAX9924UAUB+T"))
    )
  )
  (nets
    (net (code "1") (name "3.3V") (class "Default")
      (node (ref "C18") (pin "2") (pinfunction "2_2") (pintype "passive"))
      (node (ref "C20") (pin "2") (pinfunction "2_2") (pintype "passive"))
      (node (ref "C22") (pin "2") (pinfunction "2_2") (pintype "passive"))
      (node (ref "C27") (pin "1") (pinfunction "1_1") (pintype "passive"))
      (node (ref "C28") (pin "2") (pinfunction "2_2") (pintype "passive"))
      (node (ref "C29") (pin "1") (pinfunction "1_1") (pintype "passive"))
      (node (ref "C30") (pin "2") (pinfunction "2_2") (pintype "passive"))
      (node (ref "C31") (pin "1") (pinfunction "1_1") (pintype "passive"))
      (node (ref "C32") (pin "1") (pinfunction "1_1") (pintype "passive"))
      (node (ref "C33") (pin "1") (pinfunction "1_1") (pintype "passive"))
      (node (ref "C34") (pin "1") (pinfunction "1_1") (pintype "passive"))
      (node (ref "C35") (pin "1") (pinfunction "1_1") (pintype "passive"))
      (node (ref "C67") (pin "2") (pinfunction "2_2") (pintype "passive"))
      (node (ref "C69") (pin "2") (pinfunction "2_2") (pintype "passive"))
      (node (ref "C72") (pin "2") (pinfunction "2_2") (pintype "passive"))
      (node (ref "J11") (pin "5") (pinfunction "VREF_5") (pintype "passive"))
      (node (ref "LM1") (pin "7") (pinfunction "VCC_7") (pintype "passive"))
      (node (ref "LM2") (pin "7") (pinfunction "VCC_7") (pintype "passive"))
      (node (ref "LM3") (pin "7") (pinfunction "VCC_7") (pintype "passive"))
      (node (ref "LM4") (pin "7") (pinfunction "VCC_7") (pintype "passive"))
      (node (ref "R102") (pin "1") (pinfunction "1_1") (pintype "passive"))
      (node (ref "R104") (pin "1") (pinfunction "1_1") (pintype "passive"))
      (node (ref "R37") (pin "1") (pinfunction "1_1") (pintype "passive"))
      (node (ref "R4") (pin "1") (pinfunction "1_1") (pintype "passive"))
      (node (ref "R99") (pin "1") (pinfunction "1_1") (pintype "passive"))
      (node (ref "U10") (pin "2") (pinfunction "VCCB_2") (pintype "power_in"))
      (node (ref "U11") (pin "2") (pinfunction "VCCB_2") (pintype "power_in"))
      (node (ref "U13") (pin "2") (pinfunction "VCCB_2") (pintype "power_in"))
      (node (ref "U14") (pin "2") (pinfunction "VCCB_2") (pintype "power_in"))
      (node (ref "U15") (pin "2") (pinfunction "VCCB_2") (pintype "power_in"))
      (node (ref "U18") (pin "2") (pinfunction "VCCB_2") (pintype "power_in"))
      (node (ref "U2") (pin "100") (pinfunction "VDD_100") (pintype "power_in"))
      (node (ref "U2") (pin "11") (pinfunction "VDD_11") (pintype "power_in"))
      (node (ref "U2") (pin "20") (pinfunction "VREF+_20") (pintype "power_in"))
      (node (ref "U2") (pin "21") (pinfunction "VDDA_21") (pintype "power_in"))
      (node (ref "U2") (pin "27") (pinfunction "VDD_27") (pintype "power_in"))
      (node (ref "U2") (pin "48") (pinfunction "VCAP_48") (pintype "power_in"))
      (node (ref "U2") (pin "50") (pinfunction "VDD_50") (pintype "power_in"))
      (node (ref "U2") (pin "6") (pinfunction "VBAT_6") (pintype "power_in"))
      (node (ref "U2") (pin "73") (pinfunction "VCAP_73") (pintype "power_in"))
      (node (ref "U2") (pin "75") (pinfunction "VDD_75") (pintype "power_in"))
      (node (ref "U4") (pin "2") (pinfunction "VCCB_2") (pintype "power_in"))
      (node (ref "U9") (pin "2") (pinfunction "VCCB_2") (pintype "power_in"))
    )
    (net (code "2") (name "5V") (class "Default")
      (node (ref "C37") (pin "2") (pinfunction "2_2") (pintype "passive"))
      (node (ref "C38") (pin "2") (pinfunction "2_2") (pintype "passive"))
      (node (ref "C70") (pin "2") (pinfunction "2_2") (pintype "passive"))
      (node (ref "C71") (pin "2") (pinfunction "2_2") (pintype "passive"))
      (node (ref "D24") (pin "C") (pinfunction "C_C") (pintype "passive"))
      (node (ref "FL") (pin "1") (pinfunction "1_1") (pintype "passive"))
      (node (ref "J11") (pin "3") (pinfunction "VDD_3") (pintype "passive"))
      (node (ref "R1") (pin "1") (pinfunction "1_1") (pintype "passive"))
      (node (ref "R103") (pin "1") (pinfunction "1_1") (pintype "passive"))
      (node (ref "R2") (pin "1") (pinfunction "1_1") (pintype "passive"))
      (node (ref "R3") (pin "1") (pinfunction "1_1") (pintype "passive"))
      (node (ref "U1") (pin "6") (pinfunction "VDD_6") (pintype "power_in"))
      (node (ref "U8") (pin "6") (pinfunction "VDD_6") (pintype "power_in"))
    )
    (net (code "3") (name "5V_Sensor") (class "Default")
      (node (ref "C23") (pin "2") (pinfunction "2_2") (pintype "passive"))
      (node (ref "C40") (pin "2") (pinfunction "2_2") (pintype "passive"))
      (node (ref "C42") (pin "2") (pinfunction "2_2") (pintype "passive"))
      (node (ref "C58") (pin "2") (pinfunction "2_2") (pintype "passive"))
      (node (ref "C60") (pin "2") (pinfunction "2_2") (pintype "passive"))
      (node (ref "FL") (pin "2") (pinfunction "2_2") (pintype "passive"))
      (node (ref "J8") (pin "1") (pinfunction "P$1_1") (pintype "passive"))
      (node (ref "MAP1") (pin "2") (pinfunction "VCC_2") (pintype "passive"))
      (node (ref "R15") (pin "2") (pinfunction "2_2") (pintype "passive"))
      (node (ref "R35") (pin "2") (pinfunction "2_2") (pintype "passive"))
      (node (ref "R89") (pin "1") (pinfunction "1_1") (pintype "passive"))
      (node (ref "R91") (pin "1") (pinfunction "1_1") (pintype "passive"))
      (node (ref "R92") (pin "1") (pinfunction "1_1") (pintype "passive"))
      (node (ref "R97") (pin "1") (pinfunction "1_1") (pintype "passive"))
      (node (ref "U10") (pin "5") (pinfunction "VCCA_5") (pintype "power_in"))
      (node (ref "U11") (pin "5") (pinfunction "VCCA_5") (pintype "power_in"))
      (node (ref "U12") (pin "17") (pinfunction "VCC_17") (pintype "passive"))
      (node (ref "U13") (pin "5") (pinfunction "VCCA_5") (pintype "power_in"))
      (node (ref "U14") (pin "5") (pinfunction "VCCA_5") (pintype "power_in"))
      (node (ref "U15") (pin "5") (pinfunction "VCCA_5") (pintype "power_in"))
      (node (ref "U18") (pin "5") (pinfunction "VCCA_5") (pintype "power_in"))
      (node (ref "U22") (pin "10") (pinfunction "VCC_10") (pintype "power_in"))
      (node (ref "U4") (pin "5") (pinfunction "VCCA_5") (pintype "power_in"))
      (node (ref "U6") (pin "10") (pinfunction "VCC_10") (pintype "power_in"))
      (node (ref "U9") (pin "5") (pinfunction "VCCA_5") (pintype "power_in"))
    )
    (net (code "4") (name "Bat_Ground") (class "Default")
      (node (ref "C1") (pin "2") (pinfunction "2_2") (pintype "passive"))
      (node (ref "C18") (pin "1") (pinfunction "1_1") (pintype "passive"))
      (node (ref "C2") (pin "2") (pinfunction "2_2") (pintype "passive"))
      (node (ref "C20") (pin "1") (pinfunction "1_1") (pintype "passive"))
      (node (ref "C22") (pin "1") (pinfunction "1_1") (pintype "passive"))
      (node (ref "C23") (pin "1") (pinfunction "1_1") (pintype "passive"))
      (node (ref "C27") (pin "2") (pinfunction "2_2") (pintype "passive"))
      (node (ref "C28") (pin "1") (pinfunction "1_1") (pintype "passive"))
      (node (ref "C29") (pin "2") (pinfunction "2_2") (pintype "passive"))
      (node (ref "C30") (pin "1") (pinfunction "1_1") (pintype "passive"))
      (node (ref "C31") (pin "2") (pinfunction "2_2") (pintype "passive"))
      (node (ref "C32") (pin "2") (pinfunction "2_2") (pintype "passive"))
      (node (ref "C33") (pin "2") (pinfunction "2_2") (pintype "passive"))
      (node (ref "C34") (pin "2") (pinfunction "2_2") (pintype "passive"))
      (node (ref "C35") (pin "2") (pinfunction "2_2") (pintype "passive"))
      (node (ref "C36") (pin "1") (pinfunction "1_1") (pintype "passive"))
      (node (ref "C37") (pin "1") (pinfunction "1_1") (pintype "passive"))
      (node (ref "C38") (pin "1") (pinfunction "1_1") (pintype "passive"))
      (node (ref "C39") (pin "1") (pinfunction "1_1") (pintype "passive"))
      (node (ref "C40") (pin "1") (pinfunction "1_1") (pintype "passive"))
      (node (ref "C41") (pin "1") (pinfunction "1_1") (pintype "passive"))
      (node (ref "C42") (pin "1") (pinfunction "1_1") (pintype "passive"))
      (node (ref "C55") (pin "1") (pinfunction "1_1") (pintype "passive"))
      (node (ref "C56") (pin "1") (pinfunction "1_1") (pintype "passive"))
      (node (ref "C58") (pin "1") (pinfunction "1_1") (pintype "passive"))
      (node (ref "C60") (pin "1") (pinfunction "1_1") (pintype "passive"))
      (node (ref "C62") (pin "1") (pinfunction "1_1") (pintype "passive"))
      (node (ref "C63") (pin "1") (pinfunction "1_1") (pintype "passive"))
      (node (ref "C64") (pin "2") (pinfunction "2_2") (pintype "passive"))
      (node (ref "C65") (pin "2") (pinfunction "2_2") (pintype "passive"))
      (node (ref "C67") (pin "1") (pinfunction "1_1") (pintype "passive"))
      (node (ref "C68") (pin "2") (pinfunction "2_2") (pintype "passive"))
      (node (ref "C69") (pin "1") (pinfunction "1_1") (pintype "passive"))
      (node (ref "C70") (pin "1") (pinfunction "1_1") (pintype "passive"))
      (node (ref "C71") (pin "1") (pinfunction "1_1") (pintype "passive"))
      (node (ref "C72") (pin "1") (pinfunction "1_1") (pintype "passive"))
      (node (ref "D22") (pin "A") (pinfunction "A_A") (pintype "passive"))
      (node (ref "D23") (pin "A") (pinfunction "A_A") (pintype "passive"))
      (node (ref "D24") (pin "A") (pinfunction "A_A") (pintype "passive"))
      (node (ref "J11") (pin "2") (pinfunction "VSS_2") (pintype "passive"))
      (node (ref "J8") (pin "2") (pinfunction "P$2_2") (pintype "passive"))
      (node (ref "LM1") (pin "5") (pinfunction "Sens_GND_5") (pintype "passive"))
      (node (ref "LM1") (pin "6") (pinfunction "GND_6") (pintype "passive"))
      (node (ref "LM2") (pin "5") (pinfunction "Sens_GND_5") (pintype "passive"))
      (node (ref "LM2") (pin "6") (pinfunction "GND_6") (pintype "passive"))
      (node (ref "LM3") (pin "5") (pinfunction "Sens_GND_5") (pintype "passive"))
      (node (ref "LM3") (pin "6") (pinfunction "GND_6") (pintype "passive"))
      (node (ref "LM4") (pin "5") (pinfunction "Sens_GND_5") (pintype "passive"))
      (node (ref "LM4") (pin "6") (pinfunction "GND_6") (pintype "passive"))
      (node (ref "MAP1") (pin "3") (pinfunction "GND_3") (pintype "passive"))
      (node (ref "Q13") (pin "3") (pinfunction "S_3") (pintype "passive"))
      (node (ref "Q5") (pin "3") (pinfunction "E_3") (pintype "bidirectional"))
      (node (ref "Q6") (pin "3") (pinfunction "E_3") (pintype "bidirectional"))
      (node (ref "Q7") (pin "3") (pinfunction "E_3") (pintype "bidirectional"))
      (node (ref "Q8") (pin "3") (pinfunction "E_3") (pintype "bidirectional"))
      (node (ref "R100") (pin "2") (pinfunction "2_2") (pintype "passive"))
      (node (ref "R101") (pin "2") (pinfunction "2_2") (pintype "passive"))
      (node (ref "R105") (pin "2") (pinfunction "2_2") (pintype "passive"))
      (node (ref "R106") (pin "2") (pinfunction "2_2") (pintype "passive"))
      (node (ref "R107") (pin "2") (pinfunction "2_2") (pintype "passive"))
      (node (ref "R16") (pin "2") (pinfunction "2_2") (pintype "passive"))
      (node (ref "R34") (pin "2") (pinfunction "2_2") (pintype "passive"))
      (node (ref "R36") (pin "1") (pinfunction "1_1") (pintype "passive"))
      (node (ref "R40") (pin "1") (pinfunction "1_1") (pintype "passive"))
      (node (ref "R7") (pin "1") (pinfunction "1_1") (pintype "passive"))
      (node (ref "R93") (pin "1") (pinfunction "1_1") (pintype "passive"))
      (node (ref "R94") (pin "1") (pinfunction "1_1") (pintype "passive"))
      (node (ref "R95") (pin "1") (pinfunction "1_1") (pintype "passive"))
      (node (ref "R96") (pin "1") (pinfunction "1_1") (pintype "passive"))
      (node (ref "S1") (pin "3") (pinfunction "NO_3") (pintype "passive"))
      (node (ref "S1") (pin "4") (pinfunction "NO_4") (pintype "passive"))
      (node (ref "U1") (pin "3") (pinfunction "GND_3") (pintype "passive"))
      (node (ref "U10") (pin "3") (pinfunction "GND_3") (pintype "power_in"))
      (node (ref "U11") (pin "3") (pinfunction "GND_3") (pintype "power_in"))
      (node (ref "U12") (pin "24") (pinfunction "GND_24") (pintype "passive"))
      (node (ref "U12") (pin "8") (pinfunction "RST_8") (pintype "passive"))
      (node (ref "U13") (pin "3") (pinfunction "GND_3") (pintype "power_in"))
      (node (ref "U14") (pin "3") (pinfunction "GND_3") (pintype "power_in"))
      (node (ref "U15") (pin "3") (pinfunction "GND_3") (pintype "power_in"))
      (node (ref "U18") (pin "3") (pinfunction "GND_3") (pintype "power_in"))
      (node (ref "U2") (pin "10") (pinfunction "VSS_10") (pintype "power_in"))
      (node (ref "U2") (pin "19") (pinfunction "VSSA_19") (pintype "power_in"))
      (node (ref "U2") (pin "26") (pinfunction "VSS_26") (pintype "power_in"))
      (node (ref "U2") (pin "49") (pinfunction "VSS_49") (pintype "power_in"))
      (node (ref "U2") (pin "74") (pinfunction "VSS_74") (pintype "power_in"))
      (node (ref "U2") (pin "99") (pinfunction "VSS_99") (pintype "power_in"))
      (node (ref "U22") (pin "4") (pinfunction "BIAS_4") (pintype "input"))
      (node (ref "U22") (pin "5") (pinfunction "GND_5") (pintype "power_in"))
      (node (ref "U22") (pin "6") (pinfunction "ZERO_EN_6") (pintype "input"))
      (node (ref "U22") (pin "9") (pinfunction "INT_THRS_9") (pintype "input"))
      (node (ref "U4") (pin "3") (pinfunction "GND_3") (pintype "power_in"))
      (node (ref "U6") (pin "4") (pinfunction "BIAS_4") (pintype "input"))
      (node (ref "U6") (pin "5") (pinfunction "GND_5") (pintype "power_in"))
      (node (ref "U6") (pin "6") (pinfunction "ZERO_EN_6") (pintype "input"))
      (node (ref "U6") (pin "9") (pinfunction "INT_THRS_9") (pintype "input"))
      (node (ref "U8") (pin "3") (pinfunction "GND_3") (pintype "passive"))
      (node (ref "U9") (pin "3") (pinfunction "GND_3") (pintype "power_in"))
    )
    (net (code "5") (name "Bat_Voltage") (class "Default")
      (node (ref "R33") (pin "2") (pinfunction "2_2") (pintype "passive"))
      (node (ref "R34") (pin "1") (pinfunction "1_1") (pintype "passive"))
      (node (ref "U2") (pin "15") (pinfunction "PC0_15") (pintype "bidirectional"))
    )
    (net (code "6") (name "CANH") (class "Default")
      (node (ref "J11") (pin "7") (pinfunction "CANH_7") (pintype "passive"))
    )
    (net (code "7") (name "CANL") (class "Default")
      (node (ref "J11") (pin "6") (pinfunction "CANL_6") (pintype "passive"))
    )
    (net (code "8") (name "CANRX") (class "Default")
      (node (ref "J11") (pin "4") (pinfunction "RXD_4") (pintype "passive"))
      (node (ref "U2") (pin "70") (pinfunction "PA11_70") (pintype "bidirectional"))
    )
    (net (code "9") (name "CANTX") (class "Default")
      (node (ref "J11") (pin "1") (pinfunction "TXD_1") (pintype "passive"))
      (node (ref "U2") (pin "71") (pinfunction "PA12_71") (pintype "bidirectional"))
    )
    (net (code "10") (name "CJ125_DIAHG") (class "Default")
      (node (ref "Q13") (pin "1") (pinfunction "G_1") (pintype "passive"))
      (node (ref "R16") (pin "1") (pinfunction "1_1") (pintype "passive"))
      (node (ref "R27") (pin "2") (pinfunction "2_2") (pintype "passive"))
      (node (ref "U12") (pin "6") (pinfunction "DIAHG_6") (pintype "passive"))
    )
    (net (code "11") (name "CJ125_IA") (class "Default")
      (node (ref "U12") (pin "4") (pinfunction "IA_4") (pintype "passive"))
    )
    (net (code "12") (name "CJ125_IP") (class "Default")
      (node (ref "U12") (pin "3") (pinfunction "IP_3") (pintype "passive"))
    )
    (net (code "13") (name "CJ125_RS") (class "Default")
      (node (ref "U12") (pin "9") (pinfunction "RS_9") (pintype "passive"))
    )
    (net (code "14") (name "CJ125_UA") (class "Default")
      (node (ref "U12") (pin "21") (pinfunction "UA_21") (pintype "passive"))
    )
    (net (code "15") (name "CJ125_UN") (class "Default")
      (node (ref "C55") (pin "2") (pinfunction "2_2") (pintype "passive"))
      (node (ref "U12") (pin "2") (pinfunction "UN_2") (pintype "passive"))
    )
    (net (code "16") (name "CJ125_UP") (class "Default")
      (node (ref "U12") (pin "20") (pinfunction "UP_20") (pintype "passive"))
    )
    (net (code "17") (name "CJ125_UR") (class "Default")
      (node (ref "U12") (pin "12") (pinfunction "UR_12") (pintype "passive"))
    )
    (net (code "18") (name "CJ125_US") (class "Default")
      (node (ref "U12") (pin "19") (pinfunction "US_19") (pintype "passive"))
    )
    (net (code "19") (name "CJ125_VM") (class "Default")
      (node (ref "U12") (pin "18") (pinfunction "VM_18") (pintype "passive"))
    )
    (net (code "20") (name "CKP_HALL_5V_OUT") (class "Default")
      (node (ref "C63") (pin "2") (pinfunction "2_2") (pintype "passive"))
      (node (ref "R98") (pin "1") (pinfunction "1_1") (pintype "passive"))
      (node (ref "U15") (pin "4") (pinfunction "A_4") (pintype "bidirectional"))
    )
    (net (code "21") (name "CKP_HALL_IN") (class "Default")
      (node (ref "D23") (pin "C") (pinfunction "C_C") (pintype "passive"))
      (node (ref "R92") (pin "2") (pinfunction "2_2") (pintype "passive"))
      (node (ref "R98") (pin "2") (pinfunction "2_2") (pintype "passive"))
    )
    (net (code "22") (name "CKP_HALL_OUT") (class "Default")
      (node (ref "J10") (pin "3") (pinfunction "3_3") (pintype "passive"))
      (node (ref "U15") (pin "1") (pinfunction "B_1") (pintype "bidirectional"))
    )
    (net (code "23") (name "CKP_IN_1") (class "Default")
      (node (ref "C61") (pin "2") (pinfunction "2_2") (pintype "passive"))
      (node (ref "R41") (pin "1") (pinfunction "1_1") (pintype "passive"))
    )
    (net (code "24") (name "CKP_IN_2") (class "Default")
      (node (ref "C61") (pin "1") (pinfunction "1_1") (pintype "passive"))
      (node (ref "R42") (pin "1") (pinfunction "1_1") (pintype "passive"))
    )
    (net (code "25") (name "CKP_OUT") (class "Default")
      (node (ref "J10") (pin "2") (pinfunction "2_2") (pintype "passive"))
      (node (ref "R97") (pin "2") (pinfunction "2_2") (pintype "passive"))
      (node (ref "U2") (pin "22") (pinfunction "PA0_22") (pintype "bidirectional"))
    )
    (net (code "26") (name "CKP_OUT_5V") (class "Default")
      (node (ref "R35") (pin "1") (pinfunction "1_1") (pintype "passive"))
      (node (ref "U18") (pin "4") (pinfunction "A_4") (pintype "bidirectional"))
      (node (ref "U22") (pin "7") (pinfunction "COUT_7") (pintype "output"))
    )
    (net (code "27") (name "CKP_VR_OUT") (class "Default")
      (node (ref "J10") (pin "1") (pinfunction "1_1") (pintype "passive"))
      (node (ref "U18") (pin "1") (pinfunction "B_1") (pintype "bidirectional"))
    )
    (net (code "28") (name "CMP_HALL_5V_OUT") (class "Default")
      (node (ref "C62") (pin "2") (pinfunction "2_2") (pintype "passive"))
      (node (ref "R90") (pin "1") (pinfunction "1_1") (pintype "passive"))
      (node (ref "U14") (pin "4") (pinfunction "A_4") (pintype "bidirectional"))
    )
    (net (code "29") (name "CMP_HALL_IN") (class "Default")
      (node (ref "D22") (pin "C") (pinfunction "C_C") (pintype "passive"))
      (node (ref "R90") (pin "2") (pinfunction "2_2") (pintype "passive"))
      (node (ref "R91") (pin "2") (pinfunction "2_2") (pintype "passive"))
    )
    (net (code "30") (name "CMP_HALL_OUT") (class "Default")
      (node (ref "J6") (pin "3") (pinfunction "3_3") (pintype "passive"))
      (node (ref "U14") (pin "1") (pinfunction "B_1") (pintype "bidirectional"))
    )
    (net (code "31") (name "CMP_IN_1") (class "Default")
      (node (ref "C59") (pin "2") (pinfunction "2_2") (pintype "passive"))
      (node (ref "R23") (pin "1") (pinfunction "1_1") (pintype "passive"))
    )
    (net (code "32") (name "CMP_IN_2") (class "Default")
      (node (ref "C59") (pin "1") (pinfunction "1_1") (pintype "passive"))
      (node (ref "R25") (pin "1") (pinfunction "1_1") (pintype "passive"))
    )
    (net (code "33") (name "CMP_OUT") (class "Default")
      (node (ref "J6") (pin "2") (pinfunction "2_2") (pintype "passive"))
      (node (ref "R89") (pin "2") (pinfunction "2_2") (pintype "passive"))
      (node (ref "U2") (pin "23") (pinfunction "PA1_23") (pintype "bidirectional"))
    )
    (net (code "34") (name "CMP_OUT_5V") (class "Default")
      (node (ref "R15") (pin "1") (pinfunction "1_1") (pintype "passive"))
      (node (ref "U4") (pin "4") (pinfunction "A_4") (pintype "bidirectional"))
      (node (ref "U6") (pin "7") (pinfunction "COUT_7") (pintype "output"))
    )
    (net (code "35") (name "CMP_VR_OUT") (class "Default")
      (node (ref "J6") (pin "1") (pinfunction "1_1") (pintype "passive"))
      (node (ref "U4") (pin "1") (pinfunction "B_1") (pintype "bidirectional"))
    )
    (net (code "36") (name "HEATER_GND") (class "Default")
      (node (ref "Q13") (pin "2") (pinfunction "D_2") (pintype "passive"))
      (node (ref "R8") (pin "1") (pinfunction "1_1") (pintype "passive"))
    )
    (net (code "37") (name "HEATER_OUT") (class "Default")
      (node (ref "R27") (pin "1") (pinfunction "1_1") (pintype "passive"))
    )
    (net (code "38") (name "Ig_1") (class "Default")
      (node (ref "Q5") (pin "2") (pinfunction "C_2") (pintype "bidirectional"))
    )
    (net (code "39") (name "Ig_2") (class "Default")
      (node (ref "Q6") (pin "2") (pinfunction "C_2") (pintype "bidirectional"))
    )
    (net (code "40") (name "Ig_3") (class "Default")
      (node (ref "Q7") (pin "2") (pinfunction "C_2") (pintype "bidirectional"))
    )
    (net (code "41") (name "Ig_4") (class "Default")
      (node (ref "Q8") (pin "2") (pinfunction "C_2") (pintype "bidirectional"))
    )
    (net (code "42") (name "Injector_1") (class "Default")
      (node (ref "LM1") (pin "1") (pinfunction "In_1") (pintype "passive"))
      (node (ref "U2") (pin "39") (pinfunction "PE9_39") (pintype "bidirectional"))
    )
    (net (code "43") (name "Injector_2") (class "Default")
      (node (ref "LM4") (pin "1") (pinfunction "In_1") (pintype "passive"))
      (node (ref "U2") (pin "41") (pinfunction "PE11_41") (pintype "bidirectional"))
    )
    (net (code "44") (name "Injector_3") (class "Default")
      (node (ref "LM2") (pin "1") (pinfunction "In_1") (pintype "passive"))
      (node (ref "U2") (pin "43") (pinfunction "PE13_43") (pintype "bidirectional"))
    )
    (net (code "45") (name "Injector_4") (class "Default")
      (node (ref "LM3") (pin "1") (pinfunction "In_1") (pintype "passive"))
      (node (ref "U2") (pin "44") (pinfunction "PE14_44") (pintype "bidirectional"))
    )
    (net (code "46") (name "Injector_OUT_1") (class "Default")
      (node (ref "D11") (pin "C") (pinfunction "K_C") (pintype "passive"))
      (node (ref "D8") (pin "C") (pinfunction "K_C") (pintype "passive"))
      (node (ref "Q4") (pin "C") (pinfunction "C_C") (pintype "passive"))
    )
    (net (code "47") (name "Injector_OUT_2") (class "Default")
      (node (ref "D10") (pin "C") (pinfunction "K_C") (pintype "passive"))
      (node (ref "D12") (pin "C") (pinfunction "K_C") (pintype "passive"))
      (node (ref "Q9") (pin "C") (pinfunction "C_C") (pintype "passive"))
    )
    (net (code "48") (name "Injector_OUT_3") (class "Default")
      (node (ref "D2") (pin "C") (pinfunction "K_C") (pintype "passive"))
      (node (ref "D5") (pin "C") (pinfunction "K_C") (pintype "passive"))
      (node (ref "Q1") (pin "C") (pinfunction "C_C") (pintype "passive"))
    )
    (net (code "49") (name "Injector_OUT_4") (class "Default")
      (node (ref "D4") (pin "C") (pinfunction "K_C") (pintype "passive"))
      (node (ref "D6") (pin "C") (pinfunction "K_C") (pintype "passive"))
      (node (ref "Q2") (pin "C") (pinfunction "C_C") (pintype "passive"))
    )
    (net (code "50") (name "Input_Ig_1") (class "Default")
      (node (ref "R96") (pin "2") (pinfunction "2_2") (pintype "passive"))
      (node (ref "U2") (pin "59") (pinfunction "PD12_59") (pintype "bidirectional"))
      (node (ref "U8") (pin "2") (pinfunction "IN_A_2") (pintype "input"))
    )
    (net (code "51") (name "Input_Ig_2") (class "Default")
      (node (ref "R95") (pin "2") (pinfunction "2_2") (pintype "passive"))
      (node (ref "U2") (pin "60") (pinfunction "PD13_60") (pintype "bidirectional"))
      (node (ref "U8") (pin "4") (pinfunction "IN_B_4") (pintype "input"))
    )
    (net (code "52") (name "Input_Ig_3") (class "Default")
      (node (ref "R93") (pin "2") (pinfunction "2_2") (pintype "passive"))
      (node (ref "U1") (pin "2") (pinfunction "IN_A_2") (pintype "input"))
      (node (ref "U2") (pin "61") (pinfunction "PD14_61") (pintype "bidirectional"))
    )
    (net (code "53") (name "Input_Ig_4") (class "Default")
      (node (ref "R94") (pin "2") (pinfunction "2_2") (pintype "passive"))
      (node (ref "U1") (pin "4") (pinfunction "IN_B_4") (pintype "input"))
      (node (ref "U2") (pin "62") (pinfunction "PD15_62") (pintype "bidirectional"))
    )
    (net (code "54") (name "JTDI") (class "Default")
      (node (ref "U2") (pin "77") (pinfunction "PA15_77") (pintype "bidirectional"))
    )
    (net (code "55") (name "MAP_OUT") (class "Default")
      (node (ref "C39") (pin "2") (pinfunction "2_2") (pintype "passive"))
      (node (ref "MAP1") (pin "4") (pinfunction "VOUT_4") (pintype "passive"))
      (node (ref "R28") (pin "1") (pinfunction "1_1") (pintype "passive"))
      (node (ref "U2") (pin "16") (pinfunction "PC1_16") (pintype "bidirectional"))
    )
    (net (code "56") (name "Net-(C57-Pad1)") (class "Default")
      (node (ref "C57") (pin "1") (pinfunction "1_1") (pintype "passive"))
      (node (ref "R14") (pin "1") (pinfunction "1_1") (pintype "passive"))
    )
    (net (code "57") (name "Net-(D1-PadA)") (class "Default")
      (node (ref "D1") (pin "A") (pinfunction "A_A") (pintype "passive"))
      (node (ref "R1") (pin "2") (pinfunction "2_2") (pintype "passive"))
    )
    (net (code "58") (name "Net-(D1-PadC)") (class "Default")
      (node (ref "D1") (pin "C") (pinfunction "C_C") (pintype "passive"))
      (node (ref "D2") (pin "A") (pinfunction "A_A") (pintype "passive"))
    )
    (net (code "59") (name "Net-(D3-PadA)") (class "Default")
      (node (ref "D3") (pin "A") (pinfunction "A_A") (pintype "passive"))
      (node (ref "R2") (pin "2") (pinfunction "2_2") (pintype "passive"))
    )
    (net (code "60") (name "Net-(D3-PadC)") (class "Default")
      (node (ref "D3") (pin "C") (pinfunction "C_C") (pintype "passive"))
      (node (ref "D4") (pin "A") (pinfunction "A_A") (pintype "passive"))
    )
    (net (code "61") (name "Net-(D7-PadA)") (class "Default")
      (node (ref "D7") (pin "A") (pinfunction "A_A") (pintype "passive"))
      (node (ref "R3") (pin "2") (pinfunction "2_2") (pintype "passive"))
    )
    (net (code "62") (name "Net-(D7-PadC)") (class "Default")
      (node (ref "D7") (pin "C") (pinfunction "C_C") (pintype "passive"))
      (node (ref "D8") (pin "A") (pinfunction "A_A") (pintype "passive"))
    )
    (net (code "63") (name "Net-(D9-PadA)") (class "Default")
      (node (ref "D9") (pin "A") (pinfunction "A_A") (pintype "passive"))
      (node (ref "R103") (pin "2") (pinfunction "2_2") (pintype "passive"))
    )
    (net (code "64") (name "Net-(D10-PadA)") (class "Default")
      (node (ref "D10") (pin "A") (pinfunction "A_A") (pintype "passive"))
      (node (ref "D9") (pin "C") (pinfunction "C_C") (pintype "passive"))
    )
    (net (code "65") (name "Net-(J11-RS)") (class "Default")
      (node (ref "C68") (pin "1") (pinfunction "1_1") (pintype "passive"))
      (node (ref "J11") (pin "8") (pinfunction "RS_8") (pintype "passive"))
      (node (ref "R107") (pin "1") (pinfunction "1_1") (pintype "passive"))
    )
    (net (code "66") (name "Net-(LM1-Comp)") (class "Default")
      (node (ref "C3") (pin "1") (pinfunction "1_1") (pintype "passive"))
      (node (ref "LM1") (pin "3") (pinfunction "Comp_3") (pintype "passive"))
    )
    (net (code "67") (name "Net-(LM1-Out)") (class "Default")
      (node (ref "C3") (pin "2") (pinfunction "2_2") (pintype "passive"))
      (node (ref "LM1") (pin "2") (pinfunction "Out_2") (pintype "passive"))
      (node (ref "Q4") (pin "B") (pinfunction "B_B") (pintype "passive"))
    )
    (net (code "68") (name "Net-(LM1-Sens)") (class "Default")
      (node (ref "D11") (pin "A") (pinfunction "A_A") (pintype "passive"))
      (node (ref "LM1") (pin "4") (pinfunction "Sens_4") (pintype "passive"))
      (node (ref "Q4") (pin "E") (pinfunction "E_E") (pintype "passive"))
      (node (ref "R105") (pin "1") (pinfunction "1_1") (pintype "passive"))
    )
    (net (code "69") (name "Net-(LM1-TIMER)") (class "Default")
      (node (ref "C64") (pin "1") (pinfunction "1_1") (pintype "passive"))
      (node (ref "LM1") (pin "8") (pinfunction "TIMER_8") (pintype "passive"))
      (node (ref "R102") (pin "2") (pinfunction "2_2") (pintype "passive"))
    )
    (net (code "70") (name "Net-(LM2-Comp)") (class "Default")
      (node (ref "C4") (pin "1") (pinfunction "1_1") (pintype "passive"))
      (node (ref "LM2") (pin "3") (pinfunction "Comp_3") (pintype "passive"))
    )
    (net (code "71") (name "Net-(LM2-Out)") (class "Default")
      (node (ref "C4") (pin "2") (pinfunction "2_2") (pintype "passive"))
      (node (ref "LM2") (pin "2") (pinfunction "Out_2") (pintype "passive"))
      (node (ref "Q1") (pin "B") (pinfunction "B_B") (pintype "passive"))
    )
    (net (code "72") (name "Net-(LM2-Sens)") (class "Default")
      (node (ref "D5") (pin "A") (pinfunction "A_A") (pintype "passive"))
      (node (ref "LM2") (pin "4") (pinfunction "Sens_4") (pintype "passive"))
      (node (ref "Q1") (pin "E") (pinfunction "E_E") (pintype "passive"))
      (node (ref "R100") (pin "1") (pinfunction "1_1") (pintype "passive"))
    )
    (net (code "73") (name "Net-(LM2-TIMER)") (class "Default")
      (node (ref "C1") (pin "1") (pinfunction "1_1") (pintype "passive"))
      (node (ref "LM2") (pin "8") (pinfunction "TIMER_8") (pintype "passive"))
      (node (ref "R4") (pin "2") (pinfunction "2_2") (pintype "passive"))
    )
    (net (code "74") (name "Net-(LM3-Comp)") (class "Default")
      (node (ref "C17") (pin "1") (pinfunction "1_1") (pintype "passive"))
      (node (ref "LM3") (pin "3") (pinfunction "Comp_3") (pintype "passive"))
    )
    (net (code "75") (name "Net-(LM3-Out)") (class "Default")
      (node (ref "C17") (pin "2") (pinfunction "2_2") (pintype "passive"))
      (node (ref "LM3") (pin "2") (pinfunction "Out_2") (pintype "passive"))
      (node (ref "Q2") (pin "B") (pinfunction "B_B") (pintype "passive"))
    )
    (net (code "76") (name "Net-(LM3-Sens)") (class "Default")
      (node (ref "D6") (pin "A") (pinfunction "A_A") (pintype "passive"))
      (node (ref "LM3") (pin "4") (pinfunction "Sens_4") (pintype "passive"))
      (node (ref "Q2") (pin "E") (pinfunction "E_E") (pintype "passive"))
      (node (ref "R101") (pin "1") (pinfunction "1_1") (pintype "passive"))
    )
    (net (code "77") (name "Net-(LM3-TIMER)") (class "Default")
      (node (ref "C2") (pin "1") (pinfunction "1_1") (pintype "passive"))
      (node (ref "LM3") (pin "8") (pinfunction "TIMER_8") (pintype "passive"))
      (node (ref "R99") (pin "2") (pinfunction "2_2") (pintype "passive"))
    )
    (net (code "78") (name "Net-(LM4-Comp)") (class "Default")
      (node (ref "C66") (pin "1") (pinfunction "1_1") (pintype "passive"))
      (node (ref "LM4") (pin "3") (pinfunction "Comp_3") (pintype "passive"))
    )
    (net (code "79") (name "Net-(LM4-Out)") (class "Default")
      (node (ref "C66") (pin "2") (pinfunction "2_2") (pintype "passive"))
      (node (ref "LM4") (pin "2") (pinfunction "Out_2") (pintype "passive"))
      (node (ref "Q9") (pin "B") (pinfunction "B_B") (pintype "passive"))
    )
    (net (code "80") (name "Net-(LM4-Sens)") (class "Default")
      (node (ref "D12") (pin "A") (pinfunction "A_A") (pintype "passive"))
      (node (ref "LM4") (pin "4") (pinfunction "Sens_4") (pintype "passive"))
      (node (ref "Q9") (pin "E") (pinfunction "E_E") (pintype "passive"))
      (node (ref "R106") (pin "1") (pinfunction "1_1") (pintype "passive"))
    )
    (net (code "81") (name "Net-(LM4-TIMER)") (class "Default")
      (node (ref "C65") (pin "1") (pinfunction "1_1") (pintype "passive"))
      (node (ref "LM4") (pin "8") (pinfunction "TIMER_8") (pintype "passive"))
      (node (ref "R104") (pin "2") (pinfunction "2_2") (pintype "passive"))
    )
    (net (code "82") (name "Net-(Q5-G)") (class "Default")
      (node (ref "Q5") (pin "1") (pinfunction "G_1") (pintype "bidirectional"))
      (node (ref "R5") (pin "2") (pinfunction "2_2") (pintype "passive"))
    )
    (net (code "83") (name "Net-(Q6-G)") (class "Default")
      (node (ref "Q6") (pin "1") (pinfunction "G_1") (pintype "bidirectional"))
      (node (ref "R12") (pin "2") (pinfunction "2_2") (pintype "passive"))
    )
    (net (code "84") (name "Net-(Q7-G)") (class "Default")
      (node (ref "Q7") (pin "1") (pinfunction "G_1") (pintype "bidirectional"))
      (node (ref "R13") (pin "2") (pinfunction "2_2") (pintype "passive"))
    )
    (net (code "85") (name "Net-(Q8-G)") (class "Default")
      (node (ref "Q8") (pin "1") (pinfunction "G_1") (pintype "bidirectional"))
      (node (ref "R20") (pin "2") (pinfunction "2_2") (pintype "passive"))
    )
    (net (code "86") (name "Net-(U2-BOOT0)") (class "Default")
      (node (ref "R36") (pin "2") (pinfunction "2_2") (pintype "passive"))
      (node (ref "U2") (pin "94") (pinfunction "BOOT0_94") (pintype "input"))
    )
    (net (code "87") (name "Net-(U6-IN+)") (class "Default")
      (node (ref "R23") (pin "2") (pinfunction "2_2") (pintype "passive"))
      (node (ref "U6") (pin "1") (pinfunction "IN+_1") (pintype "input"))
    )
    (net (code "88") (name "Net-(U6-IN-)") (class "Default")
      (node (ref "R25") (pin "2") (pinfunction "2_2") (pintype "passive"))
      (node (ref "U6") (pin "2") (pinfunction "IN-_2") (pintype "input"))
    )
    (net (code "89") (name "Net-(U12-CF)") (class "Default")
      (node (ref "C56") (pin "2") (pinfunction "2_2") (pintype "passive"))
      (node (ref "R6") (pin "2") (pinfunction "2_2") (pintype "passive"))
      (node (ref "U12") (pin "22") (pinfunction "CF_22") (pintype "passive"))
    )
    (net (code "90") (name "Net-(U12-CM)") (class "Default")
      (node (ref "C57") (pin "2") (pinfunction "2_2") (pintype "passive"))
      (node (ref "U12") (pin "11") (pinfunction "CM_11") (pintype "passive"))
    )
    (net (code "91") (name "Net-(U12-DIAHD)") (class "Default")
      (node (ref "R8") (pin "2") (pinfunction "2_2") (pintype "passive"))
      (node (ref "U12") (pin "7") (pinfunction "DIAHD_7") (pintype "passive"))
    )
    (net (code "92") (name "Net-(U12-OSZ)") (class "Default")
      (node (ref "R7") (pin "2") (pinfunction "2_2") (pintype "passive"))
      (node (ref "U12") (pin "5") (pinfunction "OSZ_5") (pintype "passive"))
    )
    (net (code "93") (name "Net-(U12-RF)") (class "Default")
      (node (ref "R6") (pin "1") (pinfunction "1_1") (pintype "passive"))
      (node (ref "U12") (pin "23") (pinfunction "RF_23") (pintype "passive"))
    )
    (net (code "94") (name "Net-(U12-RM)") (class "Default")
      (node (ref "R14") (pin "2") (pinfunction "2_2") (pintype "passive"))
      (node (ref "U12") (pin "10") (pinfunction "RM_10") (pintype "passive"))
    )
    (net (code "95") (name "Net-(U22-IN+)") (class "Default")
      (node (ref "R41") (pin "2") (pinfunction "2_2") (pintype "passive"))
      (node (ref "U22") (pin "1") (pinfunction "IN+_1") (pintype "input"))
    )
    (net (code "96") (name "Net-(U22-IN-)") (class "Default")
      (node (ref "R42") (pin "2") (pinfunction "2_2") (pintype "passive"))
      (node (ref "U22") (pin "2") (pinfunction "IN-_2") (pintype "input"))
    )
    (net (code "97") (name "OSC_16_IN") (class "Default")
      (node (ref "U2") (pin "12") (pinfunction "PH0-OSC_IN_12") (pintype "bidirectional"))
    )
    (net (code "98") (name "OSC_16_OUT") (class "Default")
      (node (ref "U2") (pin "13") (pinfunction "PH1-OSC_OUT_13") (pintype "bidirectional"))
    )
    (net (code "99") (name "OSC_32_IN") (class "Default")
      (node (ref "U2") (pin "8") (pinfunction "PC14-OSC32_IN_8") (pintype "bidirectional"))
    )
    (net (code "100") (name "OSC_32_OUT") (class "Default")
      (node (ref "U2") (pin "9") (pinfunction "PC15-OSC32_OUT_9") (pintype "bidirectional"))
    )
    (net (code "101") (name "Output_Ig_1") (class "Default")
      (node (ref "R5") (pin "1") (pinfunction "1_1") (pintype "passive"))
      (node (ref "U8") (pin "7") (pinfunction "*OUT_A_7") (pintype "output"))
    )
    (net (code "102") (name "Output_Ig_2") (class "Default")
      (node (ref "R12") (pin "1") (pinfunction "1_1") (pintype "passive"))
      (node (ref "U8") (pin "5") (pinfunction "*OUT_B_5") (pintype "output"))
    )
    (net (code "103") (name "Output_Ig_3") (class "Default")
      (node (ref "R13") (pin "1") (pinfunction "1_1") (pintype "passive"))
      (node (ref "U1") (pin "7") (pinfunction "*OUT_A_7") (pintype "output"))
    )
    (net (code "104") (name "Output_Ig_4") (class "Default")
      (node (ref "R20") (pin "1") (pinfunction "1_1") (pintype "passive"))
      (node (ref "U1") (pin "5") (pinfunction "*OUT_B_5") (pintype "output"))
    )
    (net (code "105") (name "PWM_MCU_OUT_1") (class "Default")
      (node (ref "U2") (pin "63") (pinfunction "PC6_63") (pintype "bidirectional"))
    )
    (net (code "106") (name "PWM_MCU_OUT_2") (class "Default")
      (node (ref "U2") (pin "64") (pinfunction "PC7_64") (pintype "bidirectional"))
    )
    (net (code "107") (name "PWM_MCU_OUT_3") (class "Default")
      (node (ref "U2") (pin "91") (pinfunction "PB5_91") (pintype "bidirectional"))
    )
    (net (code "108") (name "PWM_MCU_OUT_4") (class "Default")
      (node (ref "U2") (pin "24") (pinfunction "PA2_24") (pintype "bidirectional"))
    )
    (net (code "109") (name "PWM_MCU_OUT_5") (class "Default")
      (node (ref "U2") (pin "25") (pinfunction "PA3_25") (pintype "bidirectional"))
    )
    (net (code "110") (name "PWM_MCU_OUT_6") (class "Default")
      (node (ref "U2") (pin "34") (pinfunction "PB0_34") (pintype "bidirectional"))
    )
    (net (code "111") (name "SCL_1") (class "Default")
      (node (ref "U2") (pin "92") (pinfunction "PB6_92") (pintype "bidirectional"))
    )
    (net (code "112") (name "SCL_2") (class "Default")
      (node (ref "U2") (pin "46") (pinfunction "PB10_46") (pintype "bidirectional"))
    )
    (net (code "113") (name "SDA_1") (class "Default")
      (node (ref "U2") (pin "93") (pinfunction "PB7_93") (pintype "bidirectional"))
    )
    (net (code "114") (name "SDA_2") (class "Default")
      (node (ref "U2") (pin "47") (pinfunction "PB11_47") (pintype "bidirectional"))
    )
    (net (code "115") (name "SD_CK") (class "Default")
      (node (ref "U2") (pin "80") (pinfunction "PC12_80") (pintype "bidirectional"))
    )
    (net (code "116") (name "SD_CMD") (class "Default")
      (node (ref "U2") (pin "83") (pinfunction "PD2_83") (pintype "bidirectional"))
    )
    (net (code "117") (name "SD_D0") (class "Default")
      (node (ref "U2") (pin "65") (pinfunction "PC8_65") (pintype "bidirectional"))
    )
    (net (code "118") (name "SD_D1") (class "Default")
      (node (ref "U2") (pin "66") (pinfunction "PC9_66") (pintype "bidirectional"))
    )
    (net (code "119") (name "SD_D2") (class "Default")
      (node (ref "U2") (pin "78") (pinfunction "PC10_78") (pintype "bidirectional"))
    )
    (net (code "120") (name "SD_D3") (class "Default")
      (node (ref "U2") (pin "79") (pinfunction "PC11_79") (pintype "bidirectional"))
    )
    (net (code "121") (name "SPI_MISO_CJ") (class "Default")
      (node (ref "U10") (pin "4") (pinfunction "A_4") (pintype "bidirectional"))
      (node (ref "U12") (pin "14") (pinfunction "MISO_14") (pintype "passive"))
      (node (ref "U2") (pin "90") (pinfunction "PB4_90") (pintype "bidirectional"))
    )
    (net (code "122") (name "SPI_MISO_MCU") (class "Default")
      (node (ref "U10") (pin "1") (pinfunction "B_1") (pintype "bidirectional"))
    )
    (net (code "123") (name "SPI_MOSI_CJ") (class "Default")
      (node (ref "U11") (pin "4") (pinfunction "A_4") (pintype "bidirectional"))
      (node (ref "U12") (pin "15") (pinfunction "MOSI_15") (pintype "passive"))
      (node (ref "U2") (pin "88") (pinfunction "PD7_88") (pintype "bidirectional"))
    )
    (net (code "124") (name "SPI_MOSI_MCU") (class "Default")
      (node (ref "U11") (pin "1") (pinfunction "B_1") (pintype "bidirectional"))
    )
    (net (code "125") (name "SPI_SCK_CJ") (class "Default")
      (node (ref "U12") (pin "13") (pinfunction "SCK_13") (pintype "passive"))
      (node (ref "U13") (pin "4") (pinfunction "A_4") (pintype "bidirectional"))
      (node (ref "U2") (pin "29") (pinfunction "PA5_29") (pintype "bidirectional"))
    )
    (net (code "126") (name "SPI_SCK_MCU") (class "Default")
      (node (ref "U13") (pin "1") (pinfunction "B_1") (pintype "bidirectional"))
    )
    (net (code "127") (name "SPI_SS_CJ") (class "Default")
      (node (ref "U12") (pin "16") (pinfunction "SS_16") (pintype "passive"))
      (node (ref "U2") (pin "7") (pinfunction "PC13_7") (pintype "bidirectional"))
      (node (ref "U9") (pin "4") (pinfunction "A_4") (pintype "bidirectional"))
    )
    (net (code "128") (name "SPI_SS_MCU") (class "Default")
      (node (ref "U9") (pin "1") (pinfunction "B_1") (pintype "bidirectional"))
    )
    (net (code "129") (name "SWCLK") (class "Default")
      (node (ref "U2") (pin "76") (pinfunction "PA14_76") (pintype "bidirectional"))
    )
    (net (code "130") (name "SWDIO") (class "Default")
      (node (ref "U2") (pin "72") (pinfunction "PA13_72") (pintype "bidirectional"))
    )
    (net (code "131") (name "SWO") (class "Default")
      (node (ref "U2") (pin "89") (pinfunction "PB3_89") (pintype "bidirectional"))
    )
    (net (code "132") (name "Sensor_MAP_OUT") (class "Default")
      (node (ref "R28") (pin "2") (pinfunction "2_2") (pintype "passive"))
      (node (ref "R40") (pin "2") (pinfunction "2_2") (pintype "passive"))
    )
    (net (code "133") (name "UART_1_RX") (class "Default")
      (node (ref "U2") (pin "54") (pinfunction "PB15_54") (pintype "bidirectional"))
    )
    (net (code "134") (name "UART_1_TX") (class "Default")
      (node (ref "U2") (pin "53") (pinfunction "PB14_53") (pintype "bidirectional"))
    )
    (net (code "135") (name "UART_2_RX") (class "Default")
      (node (ref "U2") (pin "56") (pinfunction "PD9_56") (pintype "bidirectional"))
    )
    (net (code "136") (name "UART_2_TX") (class "Default")
      (node (ref "U2") (pin "55") (pinfunction "PD8_55") (pintype "bidirectional"))
    )
    (net (code "137") (name "VIN") (class "Default")
      (node (ref "C41") (pin "2") (pinfunction "2_2") (pintype "passive"))
      (node (ref "R33") (pin "1") (pinfunction "1_1") (pintype "passive"))
      (node (ref "U12") (pin "1") (pinfunction "UB_1") (pintype "passive"))
    )
    (net (code "138") (name "nRESET") (class "Default")
      (node (ref "C36") (pin "2") (pinfunction "2_2") (pintype "passive"))
      (node (ref "R37") (pin "2") (pinfunction "2_2") (pintype "passive"))
      (node (ref "S1") (pin "1") (pinfunction "COM_1") (pintype "passive"))
      (node (ref "S1") (pin "2") (pinfunction "COM_2") (pintype "passive"))
      (node (ref "U2") (pin "14") (pinfunction "NRST_14") (pintype "bidirectional"))
    )
    (net (code "139") (name "unconnected-(MAP1-DNC-Pad1)") (class "Default")
      (node (ref "MAP1") (pin "1") (pinfunction "DNC_1") (pintype "passive"))
    )
    (net (code "140") (name "unconnected-(MAP1-DNC-Pad5)") (class "Default")
      (node (ref "MAP1") (pin "5") (pinfunction "DNC_5") (pintype "passive"))
    )
    (net (code "141") (name "unconnected-(MAP1-DNC-Pad6)") (class "Default")
      (node (ref "MAP1") (pin "6") (pinfunction "DNC_6") (pintype "passive"))
    )
    (net (code "142") (name "unconnected-(MAP1-DNC-Pad7)") (class "Default")
      (node (ref "MAP1") (pin "7") (pinfunction "DNC_7") (pintype "passive"))
    )
    (net (code "143") (name "unconnected-(MAP1-DNC-Pad8)") (class "Default")
      (node (ref "MAP1") (pin "8") (pinfunction "DNC_8") (pintype "passive"))
    )
    (net (code "144") (name "unconnected-(U1-NC-Pad8)") (class "Default")
      (node (ref "U1") (pin "8") (pinfunction "NC_8") (pintype "passive"))
    )
    (net (code "145") (name "unconnected-(U1-NC_2-Pad1)") (class "Default")
      (node (ref "U1") (pin "1") (pinfunction "NC_2_1") (pintype "passive"))
    )
    (net (code "146") (name "unconnected-(U2-PA4-Pad28)") (class "Default")
      (node (ref "U2") (pin "28") (pinfunction "PA4_28") (pintype "bidirectional"))
    )
    (net (code "147") (name "unconnected-(U2-PA6-Pad30)") (class "Default")
      (node (ref "U2") (pin "30") (pinfunction "PA6_30") (pintype "bidirectional"))
    )
    (net (code "148") (name "unconnected-(U2-PA7-Pad31)") (class "Default")
      (node (ref "U2") (pin "31") (pinfunction "PA7_31") (pintype "bidirectional"))
    )
    (net (code "149") (name "unconnected-(U2-PA8-Pad67)") (class "Default")
      (node (ref "U2") (pin "67") (pinfunction "PA8_67") (pintype "bidirectional"))
    )
    (net (code "150") (name "unconnected-(U2-PA9-Pad68)") (class "Default")
      (node (ref "U2") (pin "68") (pinfunction "PA9_68") (pintype "bidirectional"))
    )
    (net (code "151") (name "unconnected-(U2-PA10-Pad69)") (class "Default")
      (node (ref "U2") (pin "69") (pinfunction "PA10_69") (pintype "bidirectional"))
    )
    (net (code "152") (name "unconnected-(U2-PB1-Pad35)") (class "Default")
      (node (ref "U2") (pin "35") (pinfunction "PB1_35") (pintype "bidirectional"))
    )
    (net (code "153") (name "unconnected-(U2-PB2-Pad36)") (class "Default")
      (node (ref "U2") (pin "36") (pinfunction "PB2_36") (pintype "bidirectional"))
    )
    (net (code "154") (name "unconnected-(U2-PB8-Pad95)") (class "Default")
      (node (ref "U2") (pin "95") (pinfunction "PB8_95") (pintype "bidirectional"))
    )
    (net (code "155") (name "unconnected-(U2-PB9-Pad96)") (class "Default")
      (node (ref "U2") (pin "96") (pinfunction "PB9_96") (pintype "bidirectional"))
    )
    (net (code "156") (name "unconnected-(U2-PB12-Pad51)") (class "Default")
      (node (ref "U2") (pin "51") (pinfunction "PB12_51") (pintype "bidirectional"))
    )
    (net (code "157") (name "unconnected-(U2-PB13-Pad52)") (class "Default")
      (node (ref "U2") (pin "52") (pinfunction "PB13_52") (pintype "bidirectional"))
    )
    (net (code "158") (name "unconnected-(U2-PC2_C-Pad17)") (class "Default")
      (node (ref "U2") (pin "17") (pinfunction "PC2_C_17") (pintype "bidirectional"))
    )
    (net (code "159") (name "unconnected-(U2-PC3_C-Pad18)") (class "Default")
      (node (ref "U2") (pin "18") (pinfunction "PC3_C_18") (pintype "bidirectional"))
    )
    (net (code "160") (name "unconnected-(U2-PC4-Pad32)") (class "Default")
      (node (ref "U2") (pin "32") (pinfunction "PC4_32") (pintype "bidirectional"))
    )
    (net (code "161") (name "unconnected-(U2-PC5-Pad33)") (class "Default")
      (node (ref "U2") (pin "33") (pinfunction "PC5_33") (pintype "bidirectional"))
    )
    (net (code "162") (name "unconnected-(U2-PD0-Pad81)") (class "Default")
      (node (ref "U2") (pin "81") (pinfunction "PD0_81") (pintype "bidirectional"))
    )
    (net (code "163") (name "unconnected-(U2-PD1-Pad82)") (class "Default")
      (node (ref "U2") (pin "82") (pinfunction "PD1_82") (pintype "bidirectional"))
    )
    (net (code "164") (name "unconnected-(U2-PD3-Pad84)") (class "Default")
      (node (ref "U2") (pin "84") (pinfunction "PD3_84") (pintype "bidirectional"))
    )
    (net (code "165") (name "unconnected-(U2-PD4-Pad85)") (class "Default")
      (node (ref "U2") (pin "85") (pinfunction "PD4_85") (pintype "bidirectional"))
    )
    (net (code "166") (name "unconnected-(U2-PD5-Pad86)") (class "Default")
      (node (ref "U2") (pin "86") (pinfunction "PD5_86") (pintype "bidirectional"))
    )
    (net (code "167") (name "unconnected-(U2-PD6-Pad87)") (class "Default")
      (node (ref "U2") (pin "87") (pinfunction "PD6_87") (pintype "bidirectional"))
    )
    (net (code "168") (name "unconnected-(U2-PD10-Pad57)") (class "Default")
      (node (ref "U2") (pin "57") (pinfunction "PD10_57") (pintype "bidirectional"))
    )
    (net (code "169") (name "unconnected-(U2-PD11-Pad58)") (class "Default")
      (node (ref "U2") (pin "58") (pinfunction "PD11_58") (pintype "bidirectional"))
    )
    (net (code "170") (name "unconnected-(U2-PE0-Pad97)") (class "Default")
      (node (ref "U2") (pin "97") (pinfunction "PE0_97") (pintype "bidirectional"))
    )
    (net (code "171") (name "unconnected-(U2-PE1-Pad98)") (class "Default")
      (node (ref "U2") (pin "98") (pinfunction "PE1_98") (pintype "bidirectional"))
    )
    (net (code "172") (name "unconnected-(U2-PE2-Pad1)") (class "Default")
      (node (ref "U2") (pin "1") (pinfunction "PE2_1") (pintype "bidirectional"))
    )
    (net (code "173") (name "unconnected-(U2-PE3-Pad2)") (class "Default")
      (node (ref "U2") (pin "2") (pinfunction "PE3_2") (pintype "bidirectional"))
    )
    (net (code "174") (name "unconnected-(U2-PE4-Pad3)") (class "Default")
      (node (ref "U2") (pin "3") (pinfunction "PE4_3") (pintype "bidirectional"))
    )
    (net (code "175") (name "unconnected-(U2-PE5-Pad4)") (class "Default")
      (node (ref "U2") (pin "4") (pinfunction "PE5_4") (pintype "bidirectional"))
    )
    (net (code "176") (name "unconnected-(U2-PE6-Pad5)") (class "Default")
      (node (ref "U2") (pin "5") (pinfunction "PE6_5") (pintype "bidirectional"))
    )
    (net (code "177") (name "unconnected-(U2-PE7-Pad37)") (class "Default")
      (node (ref "U2") (pin "37") (pinfunction "PE7_37") (pintype "bidirectional"))
    )
    (net (code "178") (name "unconnected-(U2-PE8-Pad38)") (class "Default")
      (node (ref "U2") (pin "38") (pinfunction "PE8_38") (pintype "bidirectional"))
    )
    (net (code "179") (name "unconnected-(U2-PE10-Pad40)") (class "Default")
      (node (ref "U2") (pin "40") (pinfunction "PE10_40") (pintype "bidirectional"))
    )
    (net (code "180") (name "unconnected-(U2-PE12-Pad42)") (class "Default")
      (node (ref "U2") (pin "42") (pinfunction "PE12_42") (pintype "bidirectional"))
    )
    (net (code "181") (name "unconnected-(U2-PE15-Pad45)") (class "Default")
      (node (ref "U2") (pin "45") (pinfunction "PE15_45") (pintype "bidirectional"))
    )
    (net (code "182") (name "unconnected-(U6-EXT-Pad8)") (class "Default")
      (node (ref "U6") (pin "8") (pinfunction "EXT_8") (pintype "input"))
    )
    (net (code "183") (name "unconnected-(U8-NC-Pad8)") (class "Default")
      (node (ref "U8") (pin "8") (pinfunction "NC_8") (pintype "passive"))
    )
    (net (code "184") (name "unconnected-(U8-NC_2-Pad1)") (class "Default")
      (node (ref "U8") (pin "1") (pinfunction "NC_2_1") (pintype "passive"))
    )
    (net (code "185") (name "unconnected-(U22-EXT-Pad8)") (class "Default")
      (node (ref "U22") (pin "8") (pinfunction "EXT_8") (pintype "input"))
    )
  )
)
